# modul_analogin.net
KiCad netlist of a schematic drawn in EAGLE
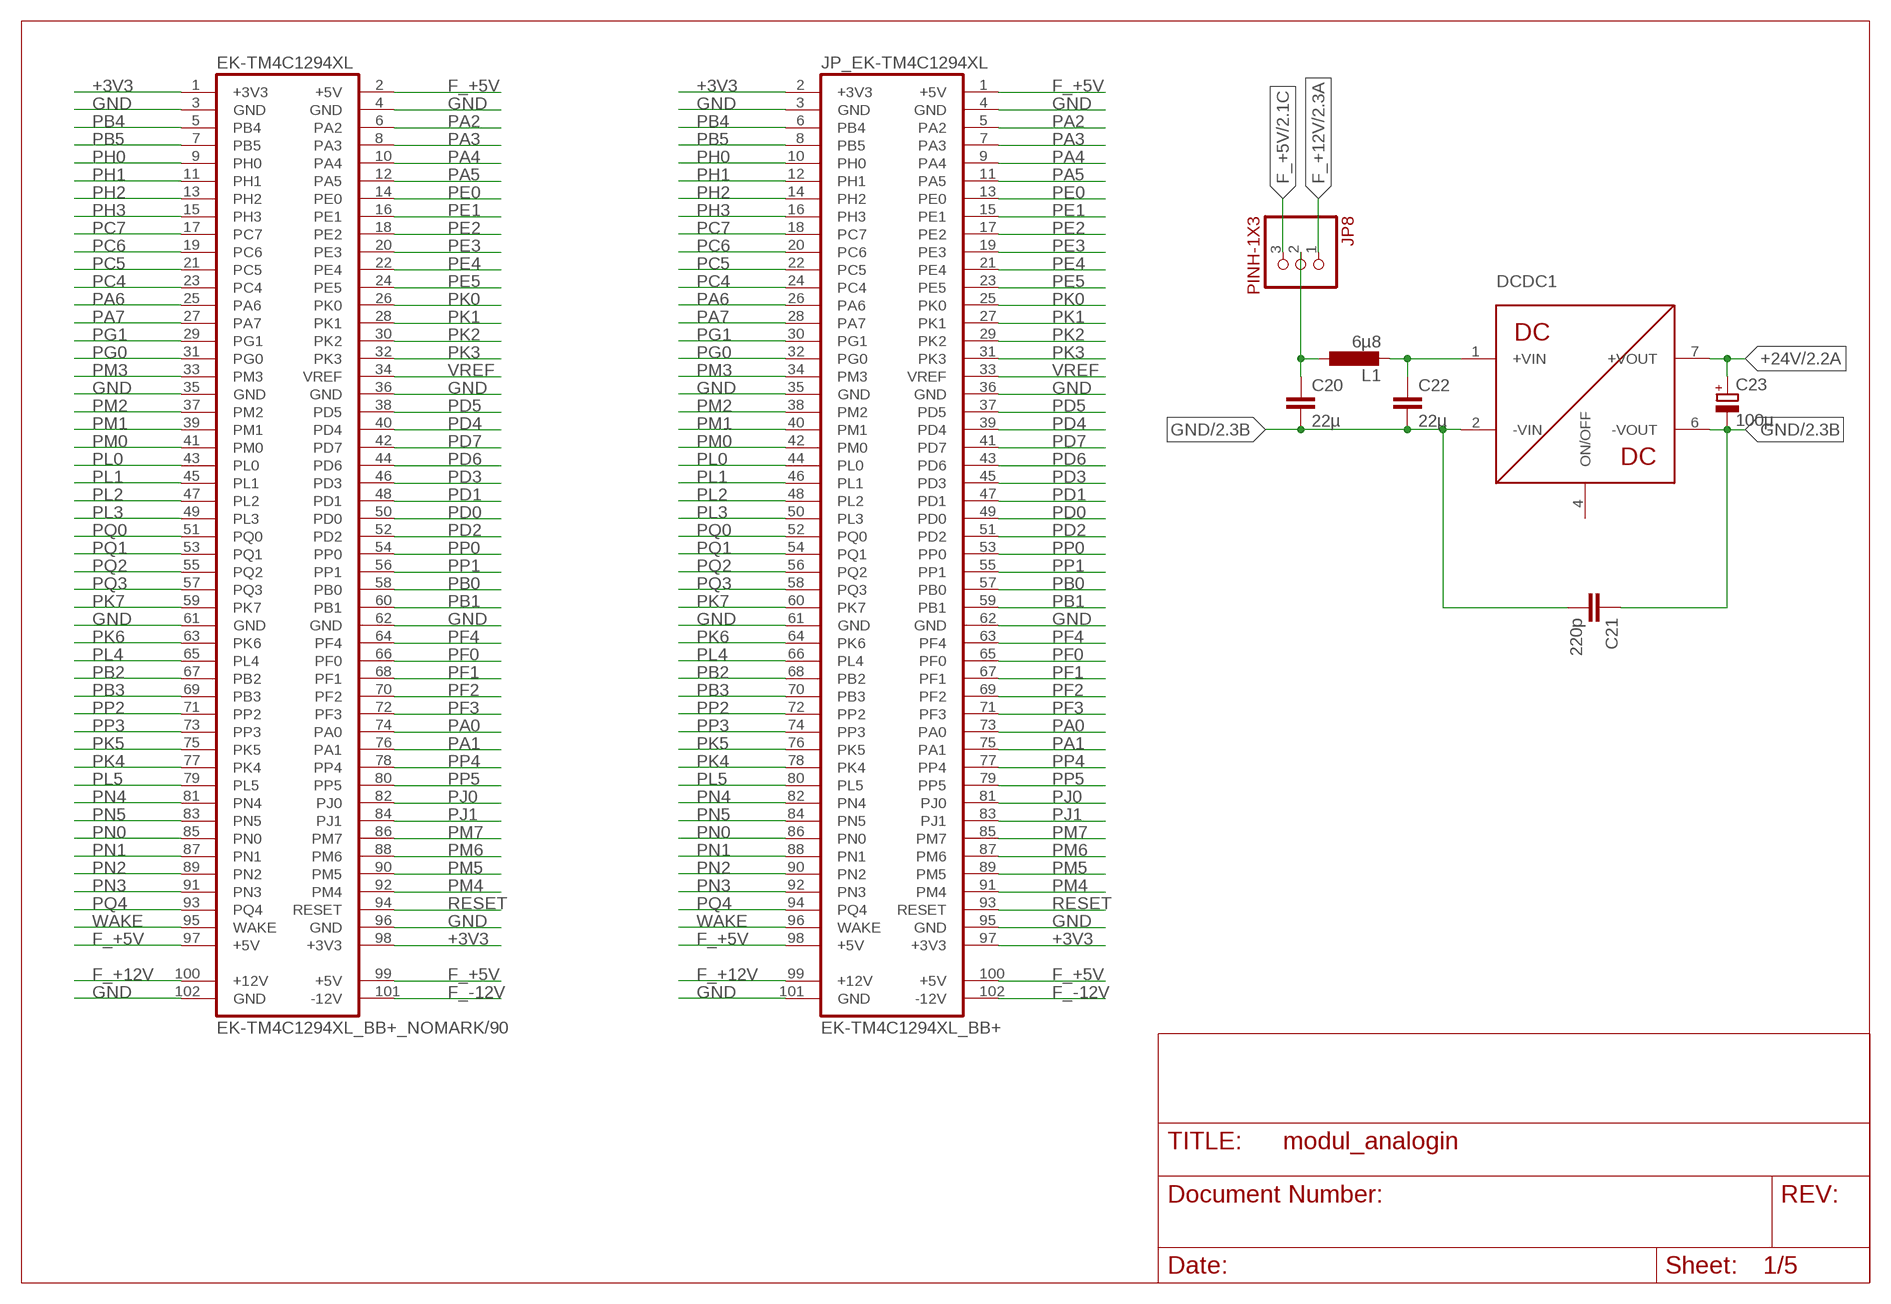
[diagram p0: schematic, sheet 1]
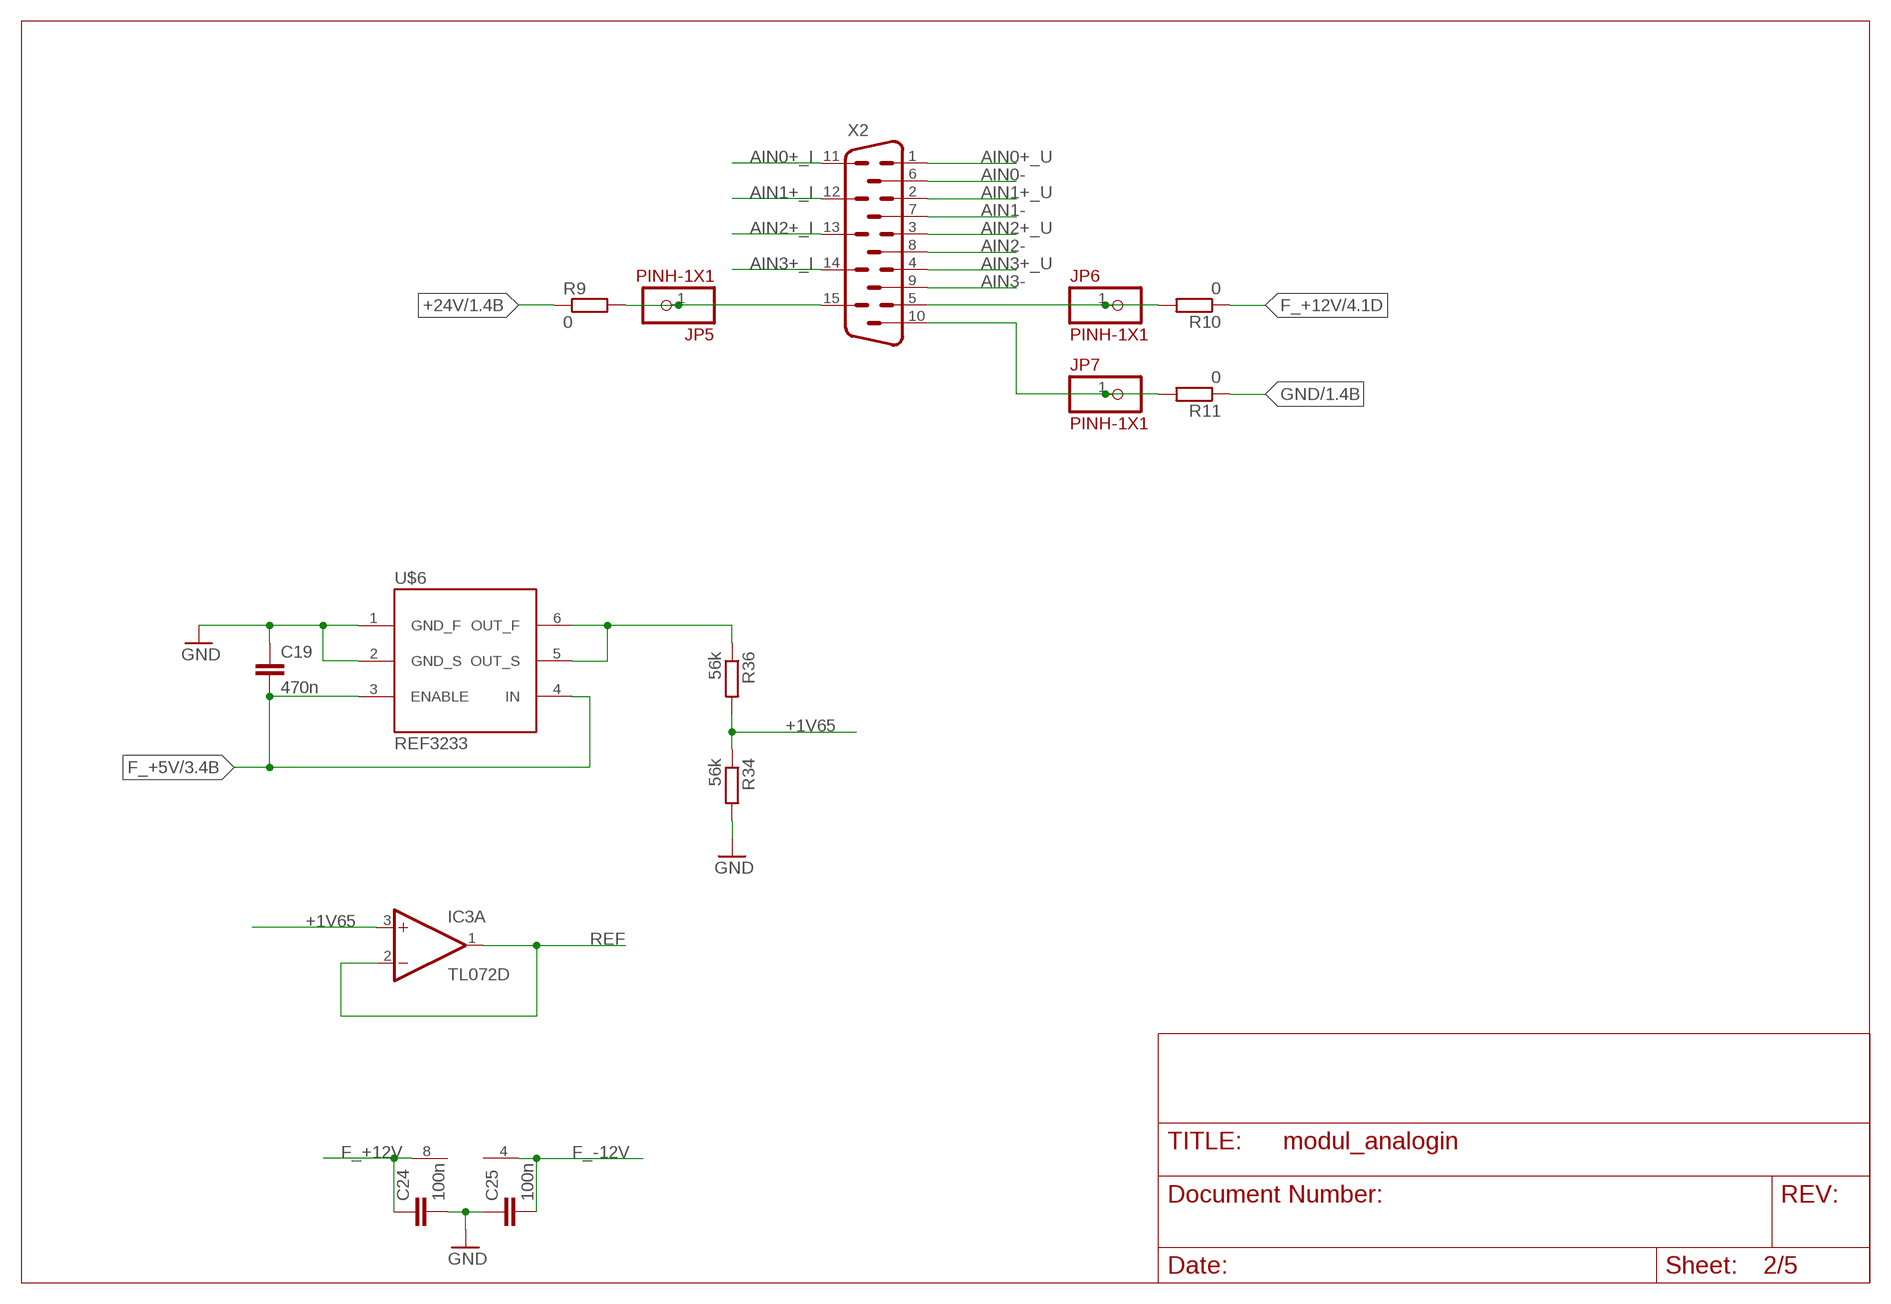
[diagram p1: schematic, sheet 2]
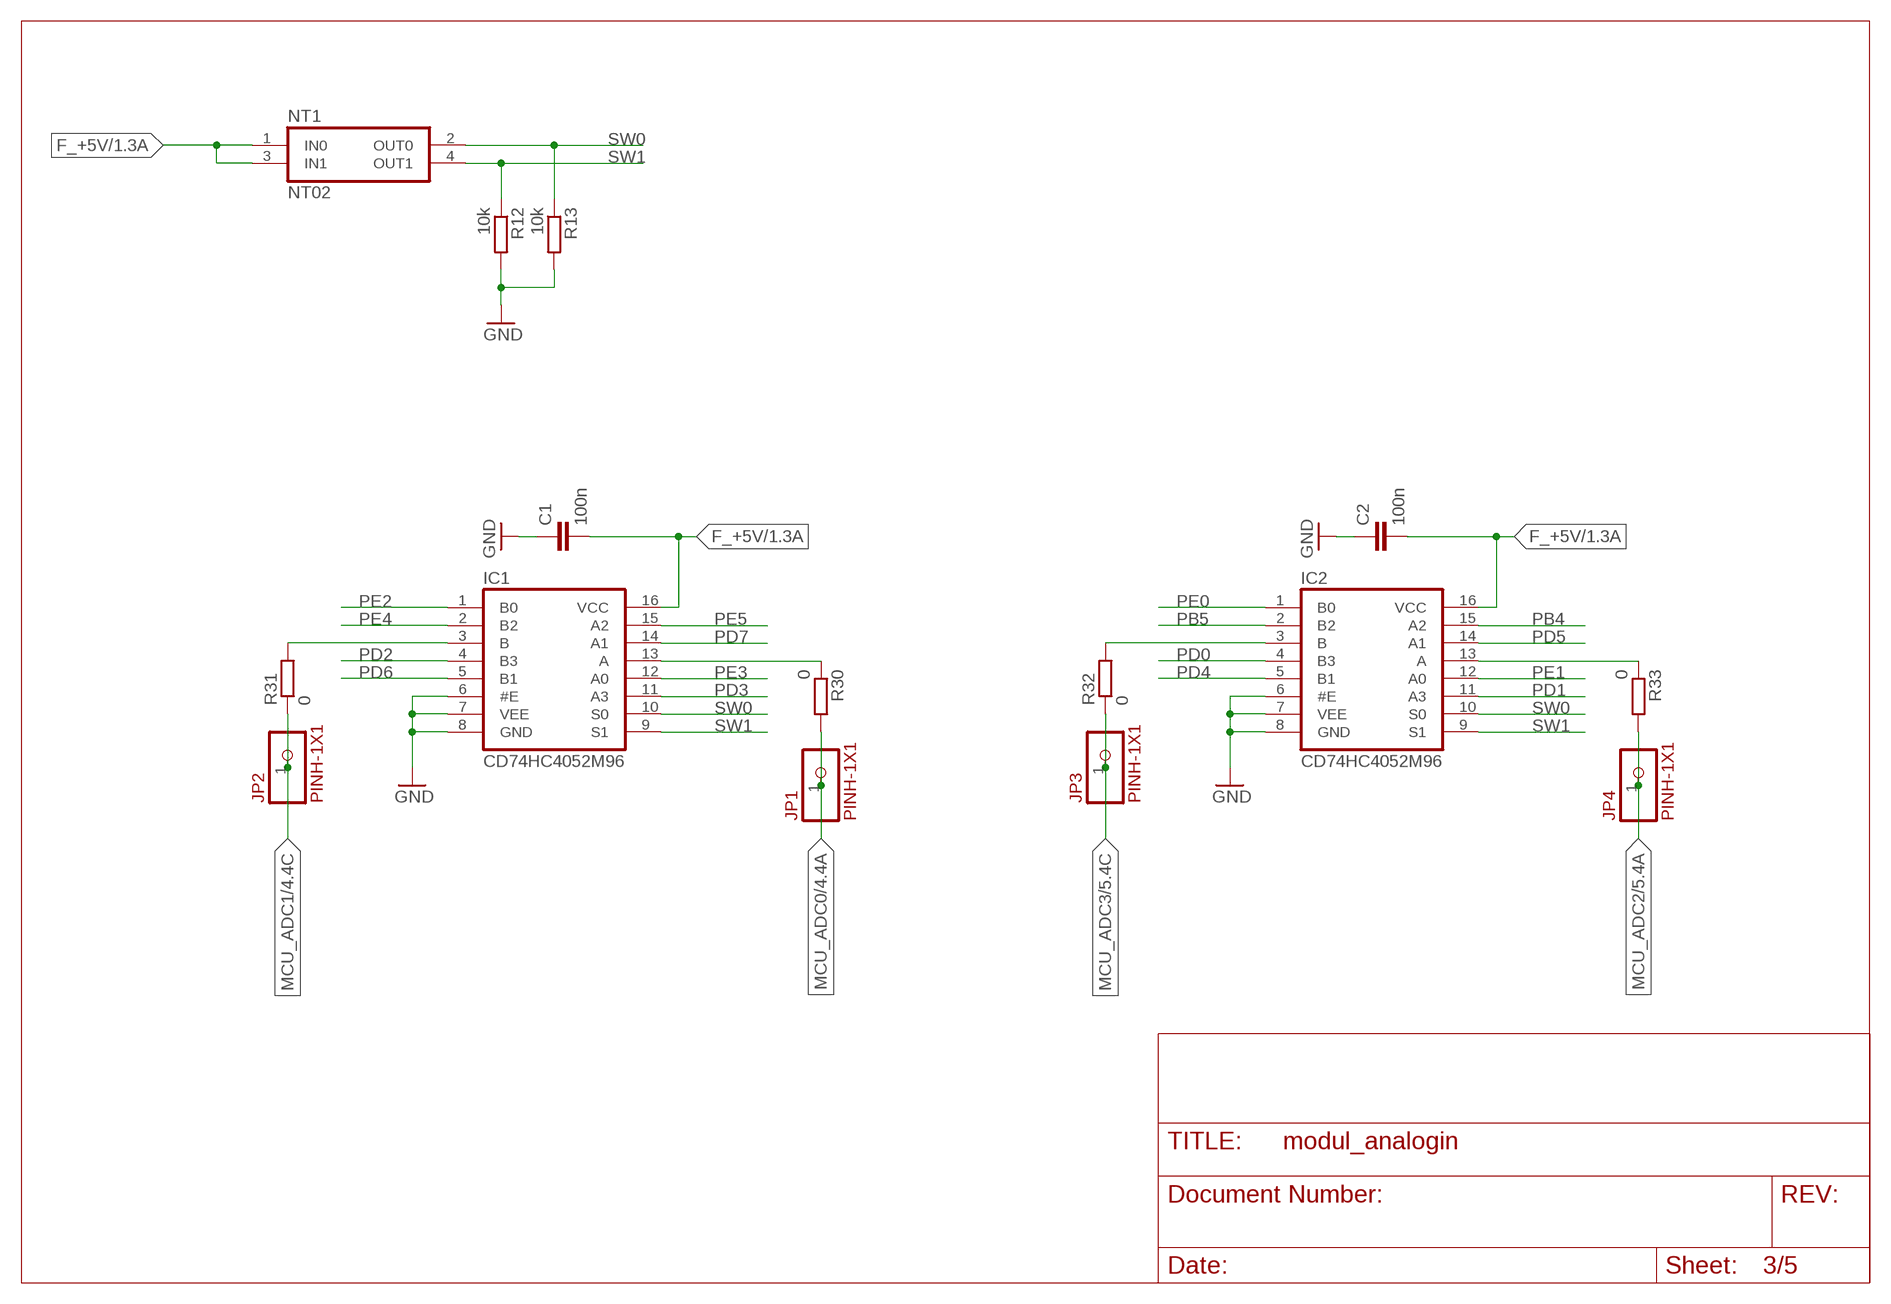
[diagram p2: schematic, sheet 3]
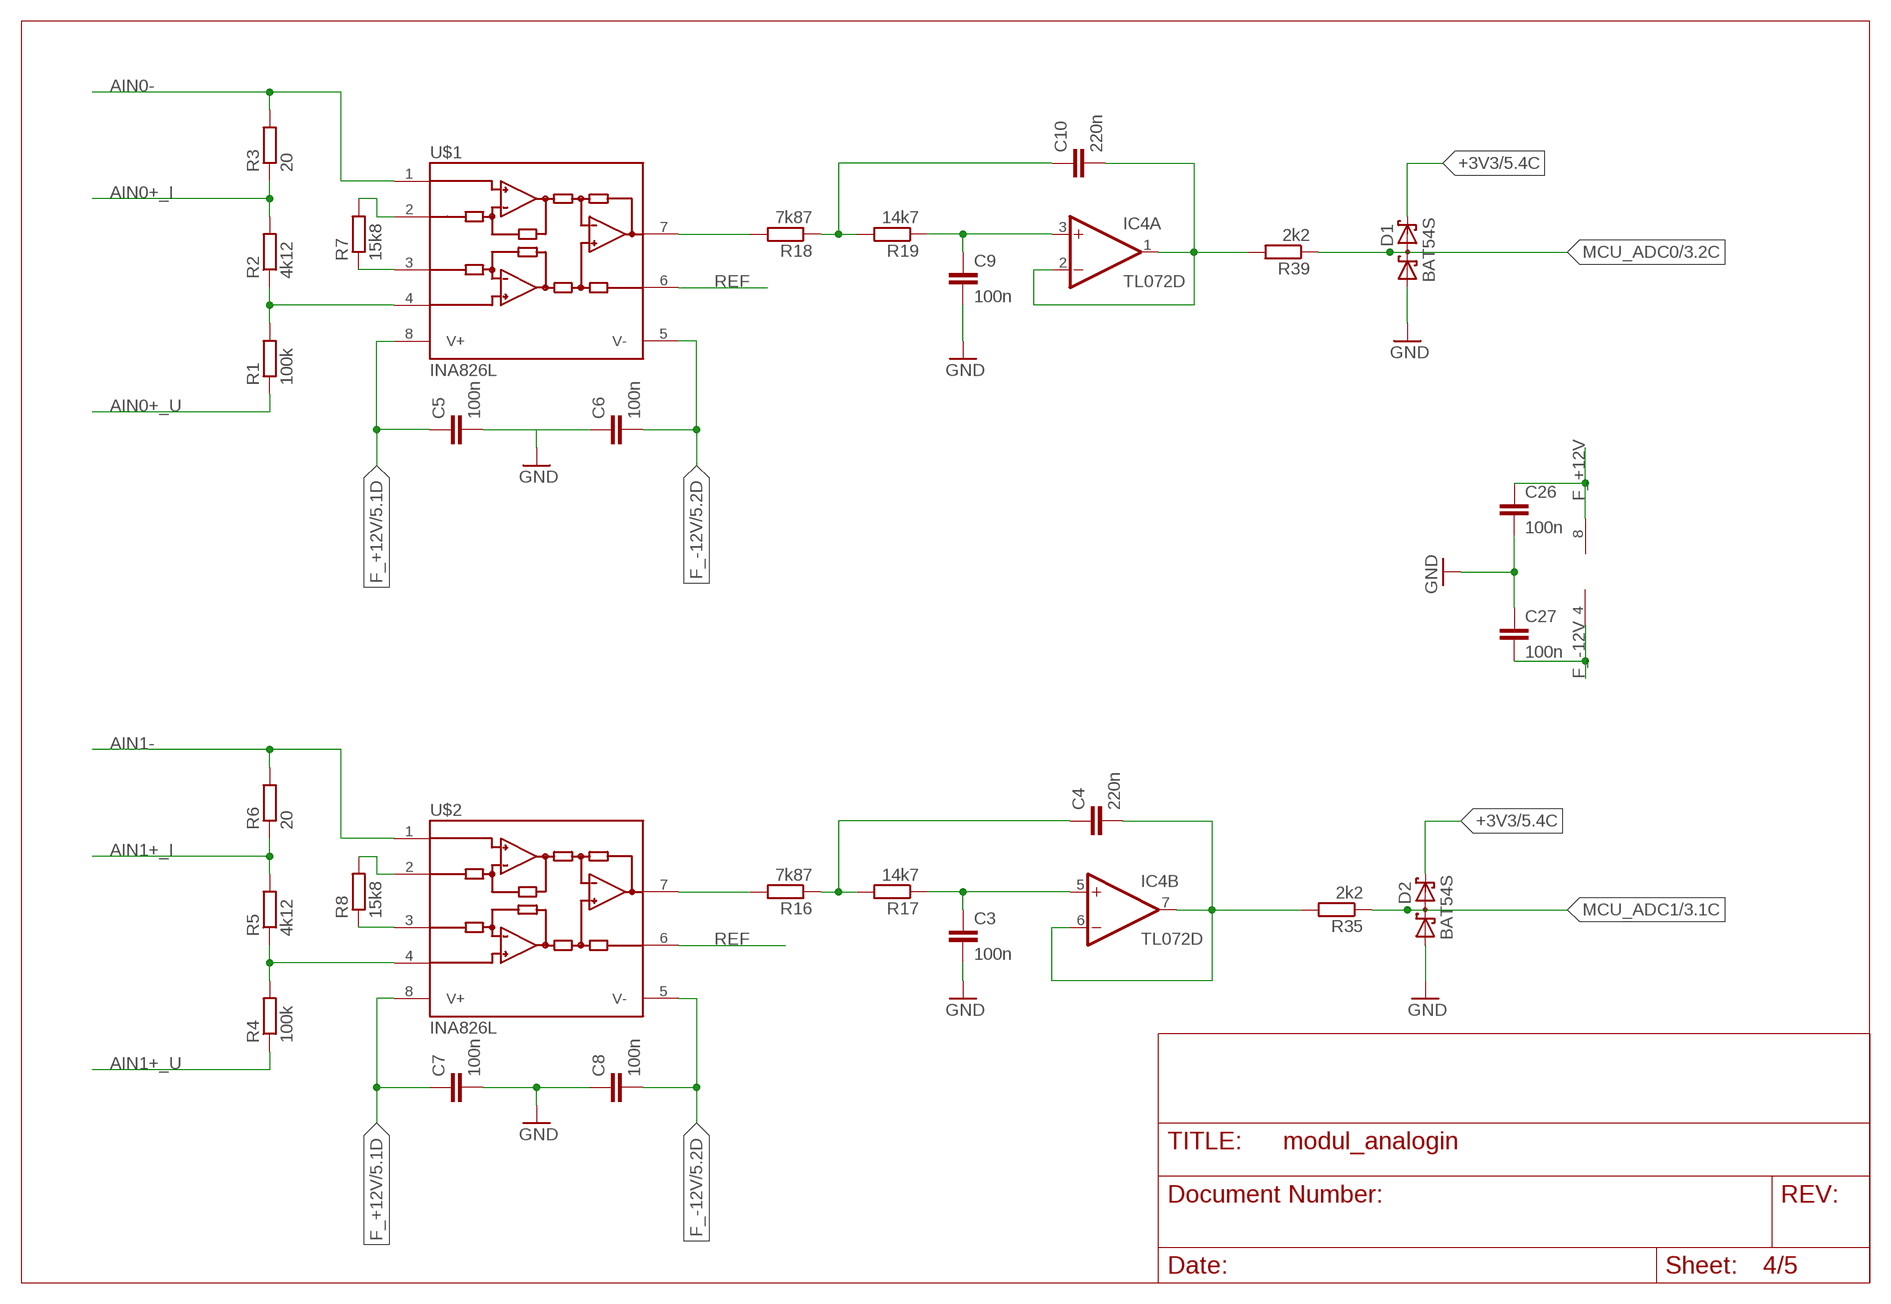
[diagram p3: schematic, sheet 4]
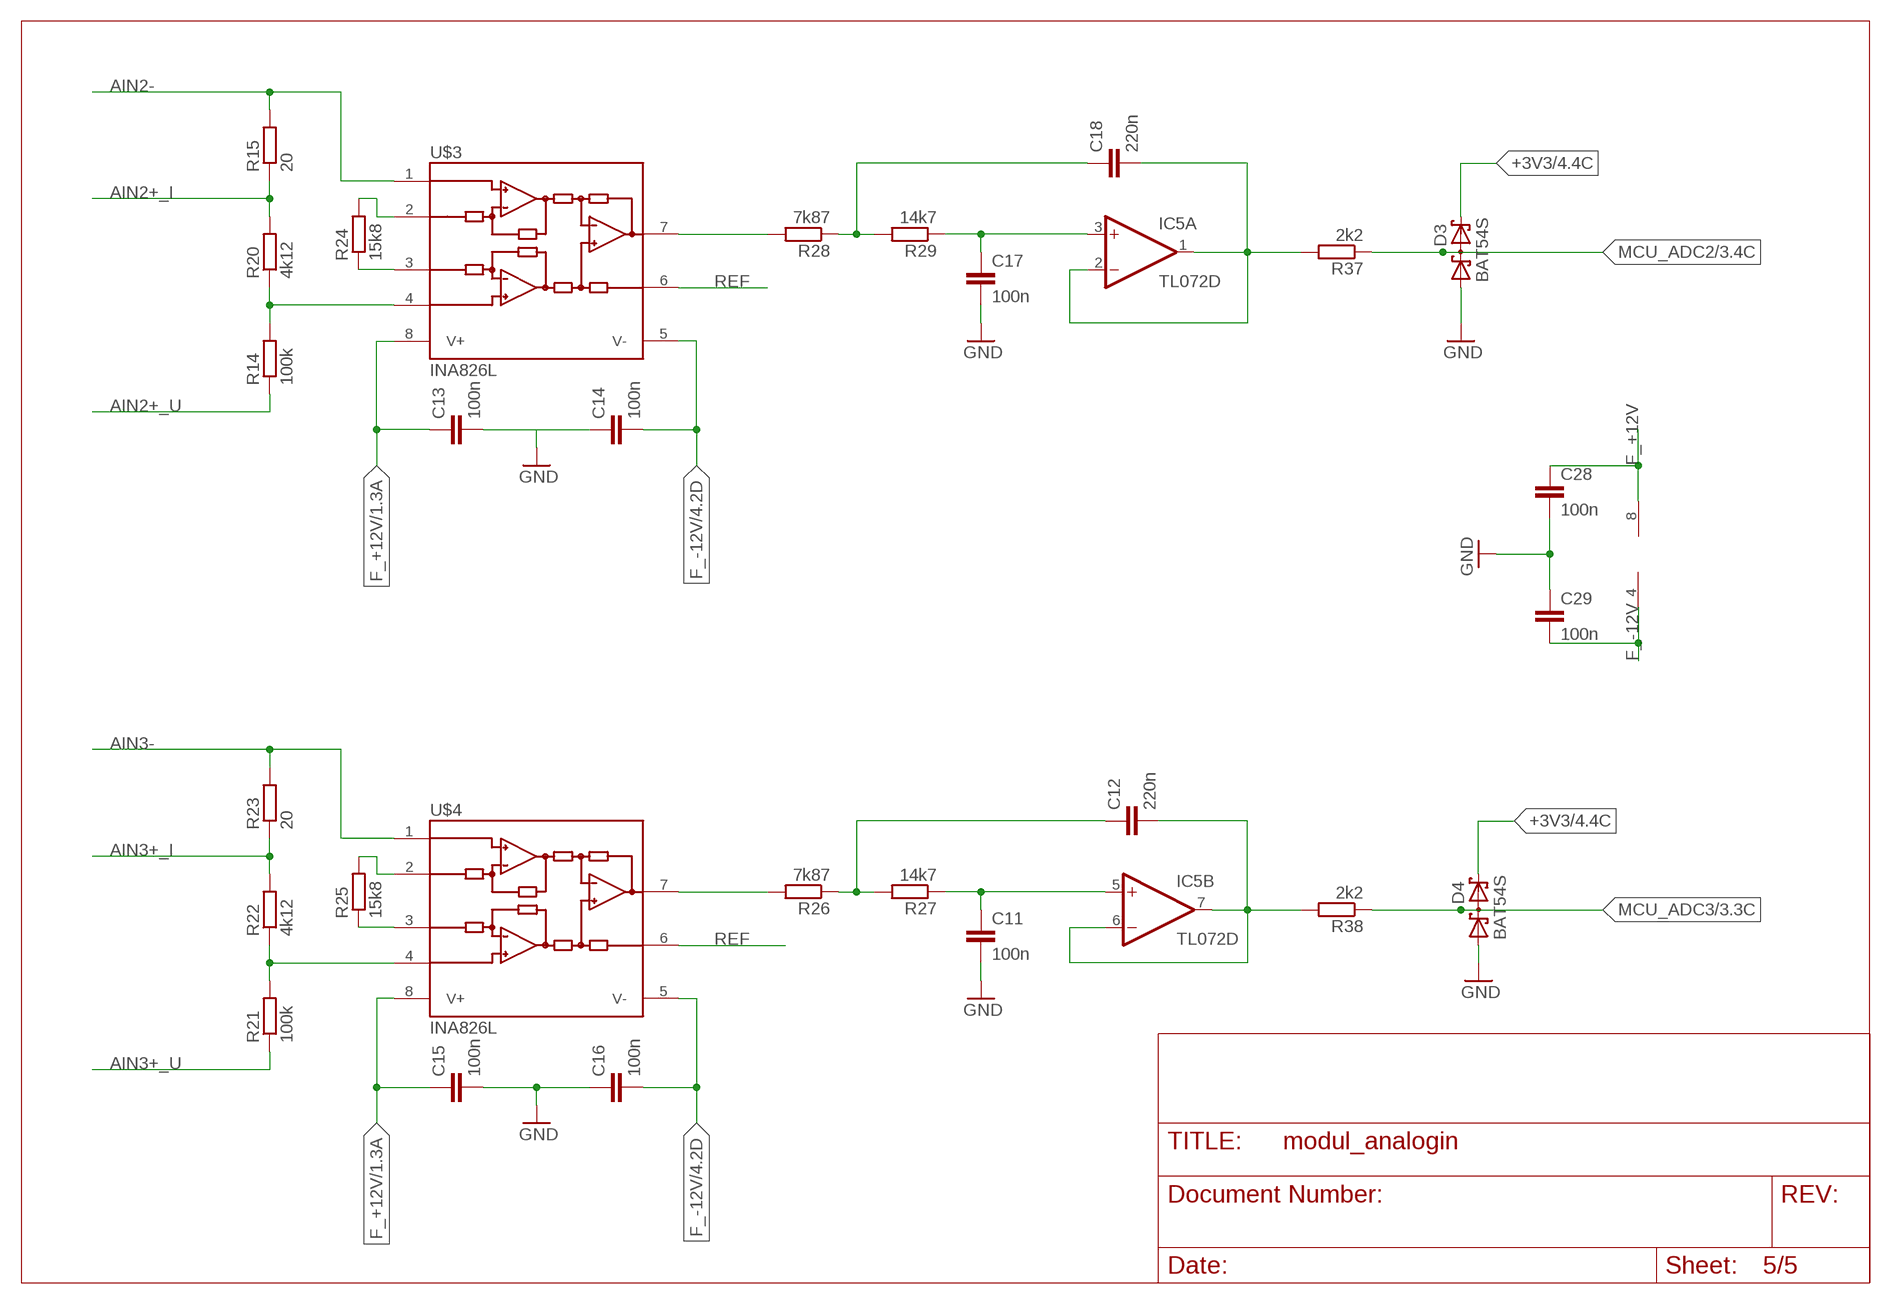
[diagram p4: schematic, sheet 5]

(export (version "E")
  (design (tool "Eeschema 10.0.6"))
  (components
    (comp (ref "C11")
      (value "100n")
      (footprint "eagle-import:C0805")
      (libsource (lib "eagle-import") (part "resistor_C-EUC0805"))
    )
    (comp (ref "C12")
      (value "220n")
      (footprint "eagle-import:C0805")
      (libsource (lib "eagle-import") (part "resistor_C-EUC0805"))
    )
    (comp (ref "C13")
      (value "100n")
      (footprint "eagle-import:C0805")
      (libsource (lib "eagle-import") (part "resistor_C-EUC0805"))
    )
    (comp (ref "C14")
      (value "100n")
      (footprint "eagle-import:C0805")
      (libsource (lib "eagle-import") (part "resistor_C-EUC0805"))
    )
    (comp (ref "C15")
      (value "100n")
      (footprint "eagle-import:C0805")
      (libsource (lib "eagle-import") (part "resistor_C-EUC0805"))
    )
    (comp (ref "C16")
      (value "100n")
      (footprint "eagle-import:C0805")
      (libsource (lib "eagle-import") (part "resistor_C-EUC0805"))
    )
    (comp (ref "C17")
      (value "100n")
      (footprint "eagle-import:C0805")
      (libsource (lib "eagle-import") (part "resistor_C-EUC0805"))
    )
    (comp (ref "C18")
      (value "220n")
      (footprint "eagle-import:C0805")
      (libsource (lib "eagle-import") (part "resistor_C-EUC0805"))
    )
    (comp (ref "C28")
      (value "100n")
      (footprint "eagle-import:C0805")
      (libsource (lib "eagle-import") (part "resistor_C-EUC0805"))
    )
    (comp (ref "C29")
      (value "100n")
      (footprint "eagle-import:C0805")
      (libsource (lib "eagle-import") (part "resistor_C-EUC0805"))
    )
    (comp (ref "D3")
      (value "BAT54S")
      (footprint "eagle-import:SOT23")
      (libsource (lib "eagle-import") (part "BAT54S"))
    )
    (comp (ref "D4")
      (value "BAT54S")
      (footprint "eagle-import:SOT23")
      (libsource (lib "eagle-import") (part "BAT54S"))
    )
    (comp (ref "IC5")
      (value "TL072D")
      (footprint "eagle-import:SO08")
      (libsource (lib "eagle-import") (part "TL072D"))
    )
    (comp (ref "R14")
      (value "100k")
      (footprint "eagle-import:R0805")
      (libsource (lib "eagle-import") (part "R-EU_R0805"))
    )
    (comp (ref "R15")
      (value "20")
      (footprint "eagle-import:R0805")
      (libsource (lib "eagle-import") (part "R-EU_R0805"))
    )
    (comp (ref "R20")
      (value "4k12")
      (footprint "eagle-import:R0805")
      (libsource (lib "eagle-import") (part "R-EU_R0805"))
    )
    (comp (ref "R21")
      (value "100k")
      (footprint "eagle-import:R0805")
      (libsource (lib "eagle-import") (part "R-EU_R0805"))
    )
    (comp (ref "R22")
      (value "4k12")
      (footprint "eagle-import:R0805")
      (libsource (lib "eagle-import") (part "R-EU_R0805"))
    )
    (comp (ref "R23")
      (value "20")
      (footprint "eagle-import:R0805")
      (libsource (lib "eagle-import") (part "R-EU_R0805"))
    )
    (comp (ref "R24")
      (value "15k8")
      (footprint "eagle-import:R0805")
      (libsource (lib "eagle-import") (part "R-EU_R0805"))
    )
    (comp (ref "R25")
      (value "15k8")
      (footprint "eagle-import:R0805")
      (libsource (lib "eagle-import") (part "R-EU_R0805"))
    )
    (comp (ref "R26")
      (value "7k87")
      (footprint "eagle-import:R0805")
      (libsource (lib "eagle-import") (part "R-EU_R0805"))
    )
    (comp (ref "R27")
      (value "14k7")
      (footprint "eagle-import:R0805")
      (libsource (lib "eagle-import") (part "R-EU_R0805"))
    )
    (comp (ref "R28")
      (value "7k87")
      (footprint "eagle-import:R0805")
      (libsource (lib "eagle-import") (part "R-EU_R0805"))
    )
    (comp (ref "R29")
      (value "14k7")
      (footprint "eagle-import:R0805")
      (libsource (lib "eagle-import") (part "R-EU_R0805"))
    )
    (comp (ref "R37")
      (value "2k2")
      (footprint "eagle-import:R0805")
      (libsource (lib "eagle-import") (part "R-EU_R0805"))
    )
    (comp (ref "R38")
      (value "2k2")
      (footprint "eagle-import:R0805")
      (libsource (lib "eagle-import") (part "R-EU_R0805"))
    )
    (comp (ref "U$3")
      (value "INA826L")
      (footprint "eagle-import:DGK_S-PDSO-G8")
      (libsource (lib "eagle-import") (part "INA826L"))
    )
    (comp (ref "U$4")
      (value "INA826L")
      (footprint "eagle-import:DGK_S-PDSO-G8")
      (libsource (lib "eagle-import") (part "INA826L"))
    )
    (comp (ref "C20")
      (value "22µ")
      (footprint "eagle-import:C1206")
      (libsource (lib "eagle-import") (part "C-EUC1206"))
    )
    (comp (ref "C21")
      (value "220p")
      (footprint "eagle-import:C1808")
      (libsource (lib "eagle-import") (part "C-EUC1808"))
    )
    (comp (ref "C22")
      (value "22µ")
      (footprint "eagle-import:C1206")
      (libsource (lib "eagle-import") (part "C-EUC1206"))
    )
    (comp (ref "C23")
      (value "100µ")
      (footprint "eagle-import:E2,5-6")
      (libsource (lib "eagle-import") (part "CPOL-EUE2.5-6"))
    )
    (comp (ref "DCDC1")
      (value "TDN3WI")
      (footprint "eagle-import:TDN_XWI")
      (libsource (lib "eagle-import") (part "TDN3WI"))
    )
    (comp (ref "EK-TM4C1294XL")
      (value "EK-TM4C1294XL_BB+_NOMARK/90")
      (footprint "eagle-import:EK-TM4C1294XL_BB+_NOMARK_90")
      (libsource (lib "eagle-import") (part "EK-TM4C1294XL_BB+_NOMARK/90"))
    )
    (comp (ref "JP8")
      (value "PINH-1X3")
      (footprint "eagle-import:1X3")
      (libsource (lib "eagle-import") (part "PINH-1X3"))
    )
    (comp (ref "JP_EK-TM4C1294XL")
      (value "EK-TM4C1294XL_BB+")
      (footprint "eagle-import:EK-TM4C1294XL_BB+")
      (libsource (lib "eagle-import") (part "EK-TM4C1294XL_BB+"))
    )
    (comp (ref "L1")
      (value "6µ8")
      (footprint "eagle-import:L1812")
      (libsource (lib "eagle-import") (part "L-EUL1812"))
    )
    (comp (ref "C3")
      (value "100n")
      (footprint "eagle-import:C0805")
      (libsource (lib "eagle-import") (part "resistor_C-EUC0805"))
    )
    (comp (ref "C4")
      (value "220n")
      (footprint "eagle-import:C0805")
      (libsource (lib "eagle-import") (part "resistor_C-EUC0805"))
    )
    (comp (ref "C5")
      (value "100n")
      (footprint "eagle-import:C0805")
      (libsource (lib "eagle-import") (part "resistor_C-EUC0805"))
    )
    (comp (ref "C6")
      (value "100n")
      (footprint "eagle-import:C0805")
      (libsource (lib "eagle-import") (part "resistor_C-EUC0805"))
    )
    (comp (ref "C7")
      (value "100n")
      (footprint "eagle-import:C0805")
      (libsource (lib "eagle-import") (part "resistor_C-EUC0805"))
    )
    (comp (ref "C8")
      (value "100n")
      (footprint "eagle-import:C0805")
      (libsource (lib "eagle-import") (part "resistor_C-EUC0805"))
    )
    (comp (ref "C9")
      (value "100n")
      (footprint "eagle-import:C0805")
      (libsource (lib "eagle-import") (part "resistor_C-EUC0805"))
    )
    (comp (ref "C10")
      (value "220n")
      (footprint "eagle-import:C0805")
      (libsource (lib "eagle-import") (part "resistor_C-EUC0805"))
    )
    (comp (ref "C26")
      (value "100n")
      (footprint "eagle-import:C0805")
      (libsource (lib "eagle-import") (part "resistor_C-EUC0805"))
    )
    (comp (ref "C27")
      (value "100n")
      (footprint "eagle-import:C0805")
      (libsource (lib "eagle-import") (part "resistor_C-EUC0805"))
    )
    (comp (ref "D1")
      (value "BAT54S")
      (footprint "eagle-import:SOT23")
      (libsource (lib "eagle-import") (part "BAT54S"))
    )
    (comp (ref "D2")
      (value "BAT54S")
      (footprint "eagle-import:SOT23")
      (libsource (lib "eagle-import") (part "BAT54S"))
    )
    (comp (ref "IC4")
      (value "TL072D")
      (footprint "eagle-import:SO08")
      (libsource (lib "eagle-import") (part "TL072D"))
    )
    (comp (ref "R1")
      (value "100k")
      (footprint "eagle-import:R0805")
      (libsource (lib "eagle-import") (part "R-EU_R0805"))
    )
    (comp (ref "R2")
      (value "4k12")
      (footprint "eagle-import:R0805")
      (libsource (lib "eagle-import") (part "R-EU_R0805"))
    )
    (comp (ref "R3")
      (value "20")
      (footprint "eagle-import:R0805")
      (libsource (lib "eagle-import") (part "R-EU_R0805"))
    )
    (comp (ref "R4")
      (value "100k")
      (footprint "eagle-import:R0805")
      (libsource (lib "eagle-import") (part "R-EU_R0805"))
    )
    (comp (ref "R5")
      (value "4k12")
      (footprint "eagle-import:R0805")
      (libsource (lib "eagle-import") (part "R-EU_R0805"))
    )
    (comp (ref "R6")
      (value "20")
      (footprint "eagle-import:R0805")
      (libsource (lib "eagle-import") (part "R-EU_R0805"))
    )
    (comp (ref "R7")
      (value "15k8")
      (footprint "eagle-import:R0805")
      (libsource (lib "eagle-import") (part "R-EU_R0805"))
    )
    (comp (ref "R8")
      (value "15k8")
      (footprint "eagle-import:R0805")
      (libsource (lib "eagle-import") (part "R-EU_R0805"))
    )
    (comp (ref "R16")
      (value "7k87")
      (footprint "eagle-import:R0805")
      (libsource (lib "eagle-import") (part "R-EU_R0805"))
    )
    (comp (ref "R17")
      (value "14k7")
      (footprint "eagle-import:R0805")
      (libsource (lib "eagle-import") (part "R-EU_R0805"))
    )
    (comp (ref "R18")
      (value "7k87")
      (footprint "eagle-import:R0805")
      (libsource (lib "eagle-import") (part "R-EU_R0805"))
    )
    (comp (ref "R19")
      (value "14k7")
      (footprint "eagle-import:R0805")
      (libsource (lib "eagle-import") (part "R-EU_R0805"))
    )
    (comp (ref "R35")
      (value "2k2")
      (footprint "eagle-import:R0805")
      (libsource (lib "eagle-import") (part "R-EU_R0805"))
    )
    (comp (ref "R39")
      (value "2k2")
      (footprint "eagle-import:R0805")
      (libsource (lib "eagle-import") (part "R-EU_R0805"))
    )
    (comp (ref "U$1")
      (value "INA826L")
      (footprint "eagle-import:DGK_S-PDSO-G8")
      (libsource (lib "eagle-import") (part "INA826L"))
    )
    (comp (ref "U$2")
      (value "INA826L")
      (footprint "eagle-import:DGK_S-PDSO-G8")
      (libsource (lib "eagle-import") (part "INA826L"))
    )
    (comp (ref "C19")
      (value "470n")
      (footprint "eagle-import:C0805")
      (libsource (lib "eagle-import") (part "resistor_C-EUC0805"))
    )
    (comp (ref "C24")
      (value "100n")
      (footprint "eagle-import:C0805")
      (libsource (lib "eagle-import") (part "resistor_C-EUC0805"))
    )
    (comp (ref "C25")
      (value "100n")
      (footprint "eagle-import:C0805")
      (libsource (lib "eagle-import") (part "resistor_C-EUC0805"))
    )
    (comp (ref "IC3")
      (value "TL072D")
      (footprint "eagle-import:SO08")
      (libsource (lib "eagle-import") (part "TL072D"))
    )
    (comp (ref "JP5")
      (value "PINH-1X1")
      (footprint "eagle-import:1X1")
      (libsource (lib "eagle-import") (part "PINH-1X1"))
    )
    (comp (ref "JP6")
      (value "PINH-1X1")
      (footprint "eagle-import:1X1")
      (libsource (lib "eagle-import") (part "PINH-1X1"))
    )
    (comp (ref "JP7")
      (value "PINH-1X1")
      (footprint "eagle-import:1X1")
      (libsource (lib "eagle-import") (part "PINH-1X1"))
    )
    (comp (ref "R9")
      (value "0")
      (footprint "eagle-import:R0805")
      (libsource (lib "eagle-import") (part "R-EU_R0805"))
    )
    (comp (ref "R10")
      (value "0")
      (footprint "eagle-import:R0805")
      (libsource (lib "eagle-import") (part "R-EU_R0805"))
    )
    (comp (ref "R11")
      (value "0")
      (footprint "eagle-import:R0805")
      (libsource (lib "eagle-import") (part "R-EU_R0805"))
    )
    (comp (ref "R34")
      (value "56k")
      (footprint "eagle-import:R0805")
      (libsource (lib "eagle-import") (part "R-EU_R0805"))
    )
    (comp (ref "R36")
      (value "56k")
      (footprint "eagle-import:R0805")
      (libsource (lib "eagle-import") (part "R-EU_R0805"))
    )
    (comp (ref "U$6")
      (value "REF3233")
      (footprint "eagle-import:SOT-23-6_DBV")
      (libsource (lib "eagle-import") (part "REF3233"))
    )
    (comp (ref "X2")
      (value "HM15H")
      (footprint "eagle-import:HDM15H")
      (libsource (lib "eagle-import") (part "HM15H"))
    )
    (comp (ref "C1")
      (value "100n")
      (footprint "eagle-import:C0805")
      (libsource (lib "eagle-import") (part "resistor_C-EUC0805"))
    )
    (comp (ref "C2")
      (value "100n")
      (footprint "eagle-import:C0805")
      (libsource (lib "eagle-import") (part "resistor_C-EUC0805"))
    )
    (comp (ref "IC1")
      (value "CD74HC4052M96")
      (footprint "eagle-import:SOIC16_D")
      (libsource (lib "eagle-import") (part "CD74HC4052M96"))
    )
    (comp (ref "IC2")
      (value "CD74HC4052M96")
      (footprint "eagle-import:SOIC16_D")
      (libsource (lib "eagle-import") (part "CD74HC4052M96"))
    )
    (comp (ref "JP1")
      (value "PINH-1X1")
      (footprint "eagle-import:1X1")
      (libsource (lib "eagle-import") (part "PINH-1X1"))
    )
    (comp (ref "JP2")
      (value "PINH-1X1")
      (footprint "eagle-import:1X1")
      (libsource (lib "eagle-import") (part "PINH-1X1"))
    )
    (comp (ref "JP3")
      (value "PINH-1X1")
      (footprint "eagle-import:1X1")
      (libsource (lib "eagle-import") (part "PINH-1X1"))
    )
    (comp (ref "JP4")
      (value "PINH-1X1")
      (footprint "eagle-import:1X1")
      (libsource (lib "eagle-import") (part "PINH-1X1"))
    )
    (comp (ref "NT1")
      (value "NT02")
      (footprint "eagle-import:NT02")
      (libsource (lib "eagle-import") (part "NT02"))
    )
    (comp (ref "R12")
      (value "10k")
      (footprint "eagle-import:R0805")
      (libsource (lib "eagle-import") (part "R-EU_R0805"))
    )
    (comp (ref "R13")
      (value "10k")
      (footprint "eagle-import:R0805")
      (libsource (lib "eagle-import") (part "R-EU_R0805"))
    )
    (comp (ref "R30")
      (value "0")
      (footprint "eagle-import:R0805")
      (libsource (lib "eagle-import") (part "R-EU_R0805"))
    )
    (comp (ref "R31")
      (value "0")
      (footprint "eagle-import:R0805")
      (libsource (lib "eagle-import") (part "R-EU_R0805"))
    )
    (comp (ref "R32")
      (value "0")
      (footprint "eagle-import:R0805")
      (libsource (lib "eagle-import") (part "R-EU_R0805"))
    )
    (comp (ref "R33")
      (value "0")
      (footprint "eagle-import:R0805")
      (libsource (lib "eagle-import") (part "R-EU_R0805"))
    )
  )
  (nets
    (net (code "1") (name "+1V65") (class "Default")
      (node (ref "IC3") (pin "3") (pinfunction "+IN_3") (pintype "input"))
      (node (ref "R34") (pin "1") (pinfunction "1_1") (pintype "passive"))
      (node (ref "R36") (pin "2") (pinfunction "2_2") (pintype "passive"))
    )
    (net (code "2") (name "+3V3") (class "Default")
      (node (ref "D1") (pin "2") (pinfunction "C2_2") (pintype "passive"))
      (node (ref "D2") (pin "2") (pinfunction "C2_2") (pintype "passive"))
      (node (ref "D3") (pin "2") (pinfunction "C2_2") (pintype "passive"))
      (node (ref "D4") (pin "2") (pinfunction "C2_2") (pintype "passive"))
      (node (ref "EK-TM4C1294XL") (pin "1") (pinfunction "+3V3_1") (pintype "power_in"))
      (node (ref "EK-TM4C1294XL") (pin "98") (pinfunction "+3V3_98") (pintype "power_in"))
      (node (ref "JP_EK-TM4C1294XL") (pin "2") (pinfunction "+3V3_2") (pintype "power_in"))
      (node (ref "JP_EK-TM4C1294XL") (pin "97") (pinfunction "+3V3_97") (pintype "power_in"))
    )
    (net (code "3") (name "+24V") (class "Default")
      (node (ref "C23") (pin "+") (pinfunction "+_+") (pintype "passive"))
      (node (ref "DCDC1") (pin "7") (pinfunction "+VOUT_7") (pintype "power_in"))
      (node (ref "R9") (pin "1") (pinfunction "1_1") (pintype "passive"))
    )
    (net (code "4") (name "AIN0+_I") (class "Default")
      (node (ref "R2") (pin "2") (pinfunction "2_2") (pintype "passive"))
      (node (ref "R3") (pin "1") (pinfunction "1_1") (pintype "passive"))
      (node (ref "X2") (pin "11") (pinfunction "11_11") (pintype "passive"))
    )
    (net (code "5") (name "AIN0+_U") (class "Default")
      (node (ref "R1") (pin "1") (pinfunction "1_1") (pintype "passive"))
      (node (ref "X2") (pin "1") (pinfunction "1_1") (pintype "passive"))
    )
    (net (code "6") (name "AIN0-") (class "Default")
      (node (ref "R3") (pin "2") (pinfunction "2_2") (pintype "passive"))
      (node (ref "U$1") (pin "1") (pinfunction "-IN_1") (pintype "input"))
      (node (ref "X2") (pin "6") (pinfunction "6_6") (pintype "passive"))
    )
    (net (code "7") (name "AIN1+_I") (class "Default")
      (node (ref "R5") (pin "2") (pinfunction "2_2") (pintype "passive"))
      (node (ref "R6") (pin "1") (pinfunction "1_1") (pintype "passive"))
      (node (ref "X2") (pin "12") (pinfunction "12_12") (pintype "passive"))
    )
    (net (code "8") (name "AIN1+_U") (class "Default")
      (node (ref "R4") (pin "1") (pinfunction "1_1") (pintype "passive"))
      (node (ref "X2") (pin "2") (pinfunction "2_2") (pintype "passive"))
    )
    (net (code "9") (name "AIN1-") (class "Default")
      (node (ref "R6") (pin "2") (pinfunction "2_2") (pintype "passive"))
      (node (ref "U$2") (pin "1") (pinfunction "-IN_1") (pintype "input"))
      (node (ref "X2") (pin "7") (pinfunction "7_7") (pintype "passive"))
    )
    (net (code "10") (name "AIN2+_I") (class "Default")
      (node (ref "R15") (pin "1") (pinfunction "1_1") (pintype "passive"))
      (node (ref "R20") (pin "2") (pinfunction "2_2") (pintype "passive"))
      (node (ref "X2") (pin "13") (pinfunction "13_13") (pintype "passive"))
    )
    (net (code "11") (name "AIN2+_U") (class "Default")
      (node (ref "R14") (pin "1") (pinfunction "1_1") (pintype "passive"))
      (node (ref "X2") (pin "3") (pinfunction "3_3") (pintype "passive"))
    )
    (net (code "12") (name "AIN2-") (class "Default")
      (node (ref "R15") (pin "2") (pinfunction "2_2") (pintype "passive"))
      (node (ref "U$3") (pin "1") (pinfunction "-IN_1") (pintype "input"))
      (node (ref "X2") (pin "8") (pinfunction "8_8") (pintype "passive"))
    )
    (net (code "13") (name "AIN3+_I") (class "Default")
      (node (ref "R22") (pin "2") (pinfunction "2_2") (pintype "passive"))
      (node (ref "R23") (pin "1") (pinfunction "1_1") (pintype "passive"))
      (node (ref "X2") (pin "14") (pinfunction "14_14") (pintype "passive"))
    )
    (net (code "14") (name "AIN3+_U") (class "Default")
      (node (ref "R21") (pin "1") (pinfunction "1_1") (pintype "passive"))
      (node (ref "X2") (pin "4") (pinfunction "4_4") (pintype "passive"))
    )
    (net (code "15") (name "AIN3-") (class "Default")
      (node (ref "R23") (pin "2") (pinfunction "2_2") (pintype "passive"))
      (node (ref "U$4") (pin "1") (pinfunction "-IN_1") (pintype "input"))
      (node (ref "X2") (pin "9") (pinfunction "9_9") (pintype "passive"))
    )
    (net (code "16") (name "F_+5V") (class "Default")
      (node (ref "C1") (pin "2") (pinfunction "2_2") (pintype "passive"))
      (node (ref "C19") (pin "2") (pinfunction "2_2") (pintype "passive"))
      (node (ref "C2") (pin "2") (pinfunction "2_2") (pintype "passive"))
      (node (ref "EK-TM4C1294XL") (pin "2") (pinfunction "+5V_2") (pintype "power_in"))
      (node (ref "EK-TM4C1294XL") (pin "97") (pinfunction "+5V_97") (pintype "power_in"))
      (node (ref "EK-TM4C1294XL") (pin "99") (pinfunction "+5V_99") (pintype "power_in"))
      (node (ref "IC1") (pin "16") (pinfunction "VCC_16") (pintype "power_in"))
      (node (ref "IC2") (pin "16") (pinfunction "VCC_16") (pintype "power_in"))
      (node (ref "JP8") (pin "3") (pinfunction "3_3") (pintype "passive"))
      (node (ref "JP_EK-TM4C1294XL") (pin "1") (pinfunction "+5V_1") (pintype "power_in"))
      (node (ref "JP_EK-TM4C1294XL") (pin "100") (pinfunction "+5V_100") (pintype "power_in"))
      (node (ref "JP_EK-TM4C1294XL") (pin "98") (pinfunction "+5V_98") (pintype "power_in"))
      (node (ref "NT1") (pin "1") (pinfunction "IN0_1") (pintype "passive"))
      (node (ref "NT1") (pin "3") (pinfunction "IN1_3") (pintype "passive"))
      (node (ref "U$6") (pin "3") (pinfunction "ENABLE_3") (pintype "bidirectional"))
      (node (ref "U$6") (pin "4") (pinfunction "IN_4") (pintype "bidirectional"))
    )
    (net (code "17") (name "F_+12V") (class "Default")
      (node (ref "C13") (pin "1") (pinfunction "1_1") (pintype "passive"))
      (node (ref "C15") (pin "1") (pinfunction "1_1") (pintype "passive"))
      (node (ref "C24") (pin "1") (pinfunction "1_1") (pintype "passive"))
      (node (ref "C26") (pin "1") (pinfunction "1_1") (pintype "passive"))
      (node (ref "C28") (pin "1") (pinfunction "1_1") (pintype "passive"))
      (node (ref "C5") (pin "1") (pinfunction "1_1") (pintype "passive"))
      (node (ref "C7") (pin "1") (pinfunction "1_1") (pintype "passive"))
      (node (ref "EK-TM4C1294XL") (pin "100") (pinfunction "+12V_100") (pintype "power_in"))
      (node (ref "IC3") (pin "8") (pinfunction "V+_8") (pintype "power_in"))
      (node (ref "IC4") (pin "8") (pinfunction "V+_8") (pintype "power_in"))
      (node (ref "IC5") (pin "8") (pinfunction "V+_8") (pintype "power_in"))
      (node (ref "JP8") (pin "1") (pinfunction "1_1") (pintype "passive"))
      (node (ref "JP_EK-TM4C1294XL") (pin "99") (pinfunction "+12V_99") (pintype "power_in"))
      (node (ref "R10") (pin "1") (pinfunction "1_1") (pintype "passive"))
      (node (ref "U$1") (pin "8") (pinfunction "V+_8") (pintype "power_in"))
      (node (ref "U$2") (pin "8") (pinfunction "V+_8") (pintype "power_in"))
      (node (ref "U$3") (pin "8") (pinfunction "V+_8") (pintype "power_in"))
      (node (ref "U$4") (pin "8") (pinfunction "V+_8") (pintype "power_in"))
    )
    (net (code "18") (name "F_-12V") (class "Default")
      (node (ref "C14") (pin "2") (pinfunction "2_2") (pintype "passive"))
      (node (ref "C16") (pin "2") (pinfunction "2_2") (pintype "passive"))
      (node (ref "C25") (pin "2") (pinfunction "2_2") (pintype "passive"))
      (node (ref "C27") (pin "2") (pinfunction "2_2") (pintype "passive"))
      (node (ref "C29") (pin "2") (pinfunction "2_2") (pintype "passive"))
      (node (ref "C6") (pin "2") (pinfunction "2_2") (pintype "passive"))
      (node (ref "C8") (pin "2") (pinfunction "2_2") (pintype "passive"))
      (node (ref "EK-TM4C1294XL") (pin "101") (pinfunction "-12V_101") (pintype "power_in"))
      (node (ref "IC3") (pin "4") (pinfunction "V-_4") (pintype "power_in"))
      (node (ref "IC4") (pin "4") (pinfunction "V-_4") (pintype "power_in"))
      (node (ref "IC5") (pin "4") (pinfunction "V-_4") (pintype "power_in"))
      (node (ref "JP_EK-TM4C1294XL") (pin "102") (pinfunction "-12V_102") (pintype "power_in"))
      (node (ref "U$1") (pin "5") (pinfunction "V-_5") (pintype "power_in"))
      (node (ref "U$2") (pin "5") (pinfunction "V-_5") (pintype "power_in"))
      (node (ref "U$3") (pin "5") (pinfunction "V-_5") (pintype "power_in"))
      (node (ref "U$4") (pin "5") (pinfunction "V-_5") (pintype "power_in"))
    )
    (net (code "19") (name "GND") (class "Default")
      (node (ref "C1") (pin "1") (pinfunction "1_1") (pintype "passive"))
      (node (ref "C11") (pin "2") (pinfunction "2_2") (pintype "passive"))
      (node (ref "C15") (pin "2") (pinfunction "2_2") (pintype "passive"))
      (node (ref "C16") (pin "1") (pinfunction "1_1") (pintype "passive"))
      (node (ref "C17") (pin "2") (pinfunction "2_2") (pintype "passive"))
      (node (ref "C19") (pin "1") (pinfunction "1_1") (pintype "passive"))
      (node (ref "C2") (pin "1") (pinfunction "1_1") (pintype "passive"))
      (node (ref "C20") (pin "2") (pinfunction "2_2") (pintype "passive"))
      (node (ref "C21") (pin "1") (pinfunction "1_1") (pintype "passive"))
      (node (ref "C21") (pin "2") (pinfunction "2_2") (pintype "passive"))
      (node (ref "C22") (pin "2") (pinfunction "2_2") (pintype "passive"))
      (node (ref "C23") (pin "-") (pinfunction "-_-") (pintype "passive"))
      (node (ref "C24") (pin "2") (pinfunction "2_2") (pintype "passive"))
      (node (ref "C25") (pin "1") (pinfunction "1_1") (pintype "passive"))
      (node (ref "C26") (pin "2") (pinfunction "2_2") (pintype "passive"))
      (node (ref "C27") (pin "1") (pinfunction "1_1") (pintype "passive"))
      (node (ref "C28") (pin "2") (pinfunction "2_2") (pintype "passive"))
      (node (ref "C29") (pin "1") (pinfunction "1_1") (pintype "passive"))
      (node (ref "C3") (pin "2") (pinfunction "2_2") (pintype "passive"))
      (node (ref "C7") (pin "2") (pinfunction "2_2") (pintype "passive"))
      (node (ref "C8") (pin "1") (pinfunction "1_1") (pintype "passive"))
      (node (ref "C9") (pin "2") (pinfunction "2_2") (pintype "passive"))
      (node (ref "D1") (pin "1") (pinfunction "A1_1") (pintype "passive"))
      (node (ref "D2") (pin "1") (pinfunction "A1_1") (pintype "passive"))
      (node (ref "D3") (pin "1") (pinfunction "A1_1") (pintype "passive"))
      (node (ref "D4") (pin "1") (pinfunction "A1_1") (pintype "passive"))
      (node (ref "DCDC1") (pin "2") (pinfunction "-VIN_2") (pintype "power_in"))
      (node (ref "DCDC1") (pin "6") (pinfunction "-VOUT_6") (pintype "power_in"))
      (node (ref "EK-TM4C1294XL") (pin "102") (pinfunction "GND_102") (pintype "power_in"))
      (node (ref "EK-TM4C1294XL") (pin "3") (pinfunction "GND_3") (pintype "power_in"))
      (node (ref "EK-TM4C1294XL") (pin "35") (pinfunction "GND_35") (pintype "power_in"))
      (node (ref "EK-TM4C1294XL") (pin "36") (pinfunction "GND_36") (pintype "power_in"))
      (node (ref "EK-TM4C1294XL") (pin "4") (pinfunction "GND_4") (pintype "power_in"))
      (node (ref "EK-TM4C1294XL") (pin "61") (pinfunction "GND_61") (pintype "power_in"))
      (node (ref "EK-TM4C1294XL") (pin "62") (pinfunction "GND_62") (pintype "power_in"))
      (node (ref "EK-TM4C1294XL") (pin "96") (pinfunction "GND_96") (pintype "power_in"))
      (node (ref "IC1") (pin "6") (pinfunction "#E_6") (pintype "input"))
      (node (ref "IC1") (pin "7") (pinfunction "VEE_7") (pintype "power_in"))
      (node (ref "IC1") (pin "8") (pinfunction "GND_8") (pintype "power_in"))
      (node (ref "IC2") (pin "6") (pinfunction "#E_6") (pintype "input"))
      (node (ref "IC2") (pin "7") (pinfunction "VEE_7") (pintype "power_in"))
      (node (ref "IC2") (pin "8") (pinfunction "GND_8") (pintype "power_in"))
      (node (ref "JP_EK-TM4C1294XL") (pin "101") (pinfunction "GND_101") (pintype "power_in"))
      (node (ref "JP_EK-TM4C1294XL") (pin "3") (pinfunction "GND_3") (pintype "power_in"))
      (node (ref "JP_EK-TM4C1294XL") (pin "35") (pinfunction "GND_35") (pintype "power_in"))
      (node (ref "JP_EK-TM4C1294XL") (pin "36") (pinfunction "GND_36") (pintype "power_in"))
      (node (ref "JP_EK-TM4C1294XL") (pin "4") (pinfunction "GND_4") (pintype "power_in"))
      (node (ref "JP_EK-TM4C1294XL") (pin "61") (pinfunction "GND_61") (pintype "power_in"))
      (node (ref "JP_EK-TM4C1294XL") (pin "62") (pinfunction "GND_62") (pintype "power_in"))
      (node (ref "JP_EK-TM4C1294XL") (pin "95") (pinfunction "GND_95") (pintype "power_in"))
      (node (ref "R11") (pin "1") (pinfunction "1_1") (pintype "passive"))
      (node (ref "R12") (pin "2") (pinfunction "2_2") (pintype "passive"))
      (node (ref "R13") (pin "2") (pinfunction "2_2") (pintype "passive"))
      (node (ref "R34") (pin "2") (pinfunction "2_2") (pintype "passive"))
      (node (ref "U$6") (pin "1") (pinfunction "GND_F_1") (pintype "bidirectional"))
      (node (ref "U$6") (pin "2") (pinfunction "GND_S_2") (pintype "bidirectional"))
    )
    (net (code "20") (name "MCU_ADC0") (class "Default")
      (node (ref "D1") (pin "3") (pinfunction "C1A2_3") (pintype "passive"))
      (node (ref "JP1") (pin "1") (pinfunction "1_1") (pintype "passive"))
      (node (ref "R30") (pin "2") (pinfunction "2_2") (pintype "passive"))
      (node (ref "R39") (pin "1") (pinfunction "1_1") (pintype "passive"))
    )
    (net (code "21") (name "MCU_ADC1") (class "Default")
      (node (ref "D2") (pin "3") (pinfunction "C1A2_3") (pintype "passive"))
      (node (ref "JP2") (pin "1") (pinfunction "1_1") (pintype "passive"))
      (node (ref "R31") (pin "1") (pinfunction "1_1") (pintype "passive"))
      (node (ref "R35") (pin "1") (pinfunction "1_1") (pintype "passive"))
    )
    (net (code "22") (name "MCU_ADC2") (class "Default")
      (node (ref "D3") (pin "3") (pinfunction "C1A2_3") (pintype "passive"))
      (node (ref "JP4") (pin "1") (pinfunction "1_1") (pintype "passive"))
      (node (ref "R33") (pin "2") (pinfunction "2_2") (pintype "passive"))
      (node (ref "R37") (pin "1") (pinfunction "1_1") (pintype "passive"))
    )
    (net (code "23") (name "MCU_ADC3") (class "Default")
      (node (ref "D4") (pin "3") (pinfunction "C1A2_3") (pintype "passive"))
      (node (ref "JP3") (pin "1") (pinfunction "1_1") (pintype "passive"))
      (node (ref "R32") (pin "1") (pinfunction "1_1") (pintype "passive"))
      (node (ref "R38") (pin "1") (pinfunction "1_1") (pintype "passive"))
    )
    (net (code "24") (name "Net-(C4-Pad1)") (class "Default")
      (node (ref "C4") (pin "1") (pinfunction "1_1") (pintype "passive"))
      (node (ref "R16") (pin "1") (pinfunction "1_1") (pintype "passive"))
      (node (ref "R17") (pin "2") (pinfunction "2_2") (pintype "passive"))
    )
    (net (code "25") (name "Net-(C5-Pad2)") (class "Default")
      (node (ref "C5") (pin "2") (pinfunction "2_2") (pintype "passive"))
      (node (ref "C6") (pin "1") (pinfunction "1_1") (pintype "passive"))
    )
    (net (code "26") (name "Net-(C10-Pad1)") (class "Default")
      (node (ref "C10") (pin "1") (pinfunction "1_1") (pintype "passive"))
      (node (ref "R18") (pin "1") (pinfunction "1_1") (pintype "passive"))
      (node (ref "R19") (pin "2") (pinfunction "2_2") (pintype "passive"))
    )
    (net (code "27") (name "Net-(C12-Pad1)") (class "Default")
      (node (ref "C12") (pin "1") (pinfunction "1_1") (pintype "passive"))
      (node (ref "R26") (pin "1") (pinfunction "1_1") (pintype "passive"))
      (node (ref "R27") (pin "2") (pinfunction "2_2") (pintype "passive"))
    )
    (net (code "28") (name "Net-(C13-Pad2)") (class "Default")
      (node (ref "C13") (pin "2") (pinfunction "2_2") (pintype "passive"))
      (node (ref "C14") (pin "1") (pinfunction "1_1") (pintype "passive"))
    )
    (net (code "29") (name "Net-(C18-Pad1)") (class "Default")
      (node (ref "C18") (pin "1") (pinfunction "1_1") (pintype "passive"))
      (node (ref "R28") (pin "1") (pinfunction "1_1") (pintype "passive"))
      (node (ref "R29") (pin "2") (pinfunction "2_2") (pintype "passive"))
    )
    (net (code "30") (name "Net-(C20-Pad1)") (class "Default")
      (node (ref "C20") (pin "1") (pinfunction "1_1") (pintype "passive"))
      (node (ref "JP8") (pin "2") (pinfunction "2_2") (pintype "passive"))
      (node (ref "L1") (pin "1") (pinfunction "1_1") (pintype "passive"))
    )
    (net (code "31") (name "Net-(DCDC1-+VIN)") (class "Default")
      (node (ref "C22") (pin "1") (pinfunction "1_1") (pintype "passive"))
      (node (ref "DCDC1") (pin "1") (pinfunction "+VIN_1") (pintype "power_in"))
      (node (ref "L1") (pin "2") (pinfunction "2_2") (pintype "passive"))
    )
    (net (code "32") (name "Net-(IC1-A)") (class "Default")
      (node (ref "IC1") (pin "13") (pinfunction "A_13") (pintype "bidirectional"))
      (node (ref "R30") (pin "1") (pinfunction "1_1") (pintype "passive"))
    )
    (net (code "33") (name "Net-(IC1-B)") (class "Default")
      (node (ref "IC1") (pin "3") (pinfunction "B_3") (pintype "bidirectional"))
      (node (ref "R31") (pin "2") (pinfunction "2_2") (pintype "passive"))
    )
    (net (code "34") (name "Net-(IC2-A)") (class "Default")
      (node (ref "IC2") (pin "13") (pinfunction "A_13") (pintype "bidirectional"))
      (node (ref "R33") (pin "1") (pinfunction "1_1") (pintype "passive"))
    )
    (net (code "35") (name "Net-(IC2-B)") (class "Default")
      (node (ref "IC2") (pin "3") (pinfunction "B_3") (pintype "bidirectional"))
      (node (ref "R32") (pin "2") (pinfunction "2_2") (pintype "passive"))
    )
    (net (code "36") (name "Net-(IC4A-+IN)") (class "Default")
      (node (ref "C9") (pin "1") (pinfunction "1_1") (pintype "passive"))
      (node (ref "IC4") (pin "3") (pinfunction "+IN_3") (pintype "input"))
      (node (ref "R19") (pin "1") (pinfunction "1_1") (pintype "passive"))
    )
    (net (code "37") (name "Net-(IC4A--IN)") (class "Default")
      (node (ref "C10") (pin "2") (pinfunction "2_2") (pintype "passive"))
      (node (ref "IC4") (pin "1") (pinfunction "OUT_1") (pintype "output"))
      (node (ref "IC4") (pin "2") (pinfunction "-IN_2") (pintype "input"))
      (node (ref "R39") (pin "2") (pinfunction "2_2") (pintype "passive"))
    )
    (net (code "38") (name "Net-(IC4B-+IN)") (class "Default")
      (node (ref "C3") (pin "1") (pinfunction "1_1") (pintype "passive"))
      (node (ref "IC4") (pin "5") (pinfunction "+IN_5") (pintype "input"))
      (node (ref "R17") (pin "1") (pinfunction "1_1") (pintype "passive"))
    )
    (net (code "39") (name "Net-(IC4B--IN)") (class "Default")
      (node (ref "C4") (pin "2") (pinfunction "2_2") (pintype "passive"))
      (node (ref "IC4") (pin "6") (pinfunction "-IN_6") (pintype "input"))
      (node (ref "IC4") (pin "7") (pinfunction "OUT_7") (pintype "output"))
      (node (ref "R35") (pin "2") (pinfunction "2_2") (pintype "passive"))
    )
    (net (code "40") (name "Net-(IC5A-+IN)") (class "Default")
      (node (ref "C17") (pin "1") (pinfunction "1_1") (pintype "passive"))
      (node (ref "IC5") (pin "3") (pinfunction "+IN_3") (pintype "input"))
      (node (ref "R29") (pin "1") (pinfunction "1_1") (pintype "passive"))
    )
    (net (code "41") (name "Net-(IC5A--IN)") (class "Default")
      (node (ref "C18") (pin "2") (pinfunction "2_2") (pintype "passive"))
      (node (ref "IC5") (pin "1") (pinfunction "OUT_1") (pintype "output"))
      (node (ref "IC5") (pin "2") (pinfunction "-IN_2") (pintype "input"))
      (node (ref "R37") (pin "2") (pinfunction "2_2") (pintype "passive"))
    )
    (net (code "42") (name "Net-(IC5B-+IN)") (class "Default")
      (node (ref "C11") (pin "1") (pinfunction "1_1") (pintype "passive"))
      (node (ref "IC5") (pin "5") (pinfunction "+IN_5") (pintype "input"))
      (node (ref "R27") (pin "1") (pinfunction "1_1") (pintype "passive"))
    )
    (net (code "43") (name "Net-(IC5B--IN)") (class "Default")
      (node (ref "C12") (pin "2") (pinfunction "2_2") (pintype "passive"))
      (node (ref "IC5") (pin "6") (pinfunction "-IN_6") (pintype "input"))
      (node (ref "IC5") (pin "7") (pinfunction "OUT_7") (pintype "output"))
      (node (ref "R38") (pin "2") (pinfunction "2_2") (pintype "passive"))
    )
    (net (code "44") (name "Net-(JP5-Pad1)") (class "Default")
      (node (ref "JP5") (pin "1") (pinfunction "1_1") (pintype "passive"))
      (node (ref "R9") (pin "2") (pinfunction "2_2") (pintype "passive"))
      (node (ref "X2") (pin "15") (pinfunction "15_15") (pintype "passive"))
    )
    (net (code "45") (name "Net-(JP6-Pad1)") (class "Default")
      (node (ref "JP6") (pin "1") (pinfunction "1_1") (pintype "passive"))
      (node (ref "R10") (pin "2") (pinfunction "2_2") (pintype "passive"))
      (node (ref "X2") (pin "5") (pinfunction "5_5") (pintype "passive"))
    )
    (net (code "46") (name "Net-(JP7-Pad1)") (class "Default")
      (node (ref "JP7") (pin "1") (pinfunction "1_1") (pintype "passive"))
      (node (ref "R11") (pin "2") (pinfunction "2_2") (pintype "passive"))
      (node (ref "X2") (pin "10") (pinfunction "10_10") (pintype "passive"))
    )
    (net (code "47") (name "Net-(R7-Pad1)") (class "Default")
      (node (ref "R7") (pin "1") (pinfunction "1_1") (pintype "passive"))
      (node (ref "U$1") (pin "3") (pinfunction "J_3") (pintype "passive"))
    )
    (net (code "48") (name "Net-(R7-Pad2)") (class "Default")
      (node (ref "R7") (pin "2") (pinfunction "2_2") (pintype "passive"))
      (node (ref "U$1") (pin "2") (pinfunction "J_2") (pintype "passive"))
    )
    (net (code "49") (name "Net-(R8-Pad1)") (class "Default")
      (node (ref "R8") (pin "1") (pinfunction "1_1") (pintype "passive"))
      (node (ref "U$2") (pin "3") (pinfunction "J_3") (pintype "passive"))
    )
    (net (code "50") (name "Net-(R8-Pad2)") (class "Default")
      (node (ref "R8") (pin "2") (pinfunction "2_2") (pintype "passive"))
      (node (ref "U$2") (pin "2") (pinfunction "J_2") (pintype "passive"))
    )
    (net (code "51") (name "Net-(R24-Pad1)") (class "Default")
      (node (ref "R24") (pin "1") (pinfunction "1_1") (pintype "passive"))
      (node (ref "U$3") (pin "3") (pinfunction "J_3") (pintype "passive"))
    )
    (net (code "52") (name "Net-(R24-Pad2)") (class "Default")
      (node (ref "R24") (pin "2") (pinfunction "2_2") (pintype "passive"))
      (node (ref "U$3") (pin "2") (pinfunction "J_2") (pintype "passive"))
    )
    (net (code "53") (name "Net-(R25-Pad1)") (class "Default")
      (node (ref "R25") (pin "1") (pinfunction "1_1") (pintype "passive"))
      (node (ref "U$4") (pin "3") (pinfunction "J_3") (pintype "passive"))
    )
    (net (code "54") (name "Net-(R25-Pad2)") (class "Default")
      (node (ref "R25") (pin "2") (pinfunction "2_2") (pintype "passive"))
      (node (ref "U$4") (pin "2") (pinfunction "J_2") (pintype "passive"))
    )
    (net (code "55") (name "Net-(U$1-+IN)") (class "Default")
      (node (ref "R1") (pin "2") (pinfunction "2_2") (pintype "passive"))
      (node (ref "R2") (pin "1") (pinfunction "1_1") (pintype "passive"))
      (node (ref "U$1") (pin "4") (pinfunction "+IN_4") (pintype "input"))
    )
    (net (code "56") (name "Net-(U$1-OUT)") (class "Default")
      (node (ref "R18") (pin "2") (pinfunction "2_2") (pintype "passive"))
      (node (ref "U$1") (pin "7") (pinfunction "OUT_7") (pintype "output"))
    )
    (net (code "57") (name "Net-(U$2-+IN)") (class "Default")
      (node (ref "R4") (pin "2") (pinfunction "2_2") (pintype "passive"))
      (node (ref "R5") (pin "1") (pinfunction "1_1") (pintype "passive"))
      (node (ref "U$2") (pin "4") (pinfunction "+IN_4") (pintype "input"))
    )
    (net (code "58") (name "Net-(U$2-OUT)") (class "Default")
      (node (ref "R16") (pin "2") (pinfunction "2_2") (pintype "passive"))
      (node (ref "U$2") (pin "7") (pinfunction "OUT_7") (pintype "output"))
    )
    (net (code "59") (name "Net-(U$3-+IN)") (class "Default")
      (node (ref "R14") (pin "2") (pinfunction "2_2") (pintype "passive"))
      (node (ref "R20") (pin "1") (pinfunction "1_1") (pintype "passive"))
      (node (ref "U$3") (pin "4") (pinfunction "+IN_4") (pintype "input"))
    )
    (net (code "60") (name "Net-(U$3-OUT)") (class "Default")
      (node (ref "R28") (pin "2") (pinfunction "2_2") (pintype "passive"))
      (node (ref "U$3") (pin "7") (pinfunction "OUT_7") (pintype "output"))
    )
    (net (code "61") (name "Net-(U$4-+IN)") (class "Default")
      (node (ref "R21") (pin "2") (pinfunction "2_2") (pintype "passive"))
      (node (ref "R22") (pin "1") (pinfunction "1_1") (pintype "passive"))
      (node (ref "U$4") (pin "4") (pinfunction "+IN_4") (pintype "input"))
    )
    (net (code "62") (name "Net-(U$4-OUT)") (class "Default")
      (node (ref "R26") (pin "2") (pinfunction "2_2") (pintype "passive"))
      (node (ref "U$4") (pin "7") (pinfunction "OUT_7") (pintype "output"))
    )
    (net (code "63") (name "Net-(U$6-OUT_F)") (class "Default")
      (node (ref "R36") (pin "1") (pinfunction "1_1") (pintype "passive"))
      (node (ref "U$6") (pin "5") (pinfunction "OUT_S_5") (pintype "bidirectional"))
      (node (ref "U$6") (pin "6") (pinfunction "OUT_F_6") (pintype "bidirectional"))
    )
    (net (code "64") (name "PA0") (class "Default")
      (node (ref "EK-TM4C1294XL") (pin "74") (pinfunction "PA0_74") (pintype "bidirectional"))
      (node (ref "JP_EK-TM4C1294XL") (pin "73") (pinfunction "PA0_73") (pintype "bidirectional"))
    )
    (net (code "65") (name "PA1") (class "Default")
      (node (ref "EK-TM4C1294XL") (pin "76") (pinfunction "PA1_76") (pintype "bidirectional"))
      (node (ref "JP_EK-TM4C1294XL") (pin "75") (pinfunction "PA1_75") (pintype "bidirectional"))
    )
    (net (code "66") (name "PA2") (class "Default")
      (node (ref "EK-TM4C1294XL") (pin "6") (pinfunction "PA2_6") (pintype "bidirectional"))
      (node (ref "JP_EK-TM4C1294XL") (pin "5") (pinfunction "PA2_5") (pintype "bidirectional"))
    )
    (net (code "67") (name "PA3") (class "Default")
      (node (ref "EK-TM4C1294XL") (pin "8") (pinfunction "PA3_8") (pintype "bidirectional"))
      (node (ref "JP_EK-TM4C1294XL") (pin "7") (pinfunction "PA3_7") (pintype "bidirectional"))
    )
    (net (code "68") (name "PA4") (class "Default")
      (node (ref "EK-TM4C1294XL") (pin "10") (pinfunction "PA4_10") (pintype "bidirectional"))
      (node (ref "JP_EK-TM4C1294XL") (pin "9") (pinfunction "PA4_9") (pintype "bidirectional"))
    )
    (net (code "69") (name "PA5") (class "Default")
      (node (ref "EK-TM4C1294XL") (pin "12") (pinfunction "PA5_12") (pintype "bidirectional"))
      (node (ref "JP_EK-TM4C1294XL") (pin "11") (pinfunction "PA5_11") (pintype "bidirectional"))
    )
    (net (code "70") (name "PA6") (class "Default")
      (node (ref "EK-TM4C1294XL") (pin "25") (pinfunction "PA6_25") (pintype "bidirectional"))
      (node (ref "JP_EK-TM4C1294XL") (pin "26") (pinfunction "PA6_26") (pintype "bidirectional"))
    )
    (net (code "71") (name "PA7") (class "Default")
      (node (ref "EK-TM4C1294XL") (pin "27") (pinfunction "PA7_27") (pintype "bidirectional"))
      (node (ref "JP_EK-TM4C1294XL") (pin "28") (pinfunction "PA7_28") (pintype "bidirectional"))
    )
    (net (code "72") (name "PB0") (class "Default")
      (node (ref "EK-TM4C1294XL") (pin "58") (pinfunction "PB0_58") (pintype "bidirectional"))
      (node (ref "JP_EK-TM4C1294XL") (pin "57") (pinfunction "PB0_57") (pintype "bidirectional"))
    )
    (net (code "73") (name "PB1") (class "Default")
      (node (ref "EK-TM4C1294XL") (pin "60") (pinfunction "PB1_60") (pintype "bidirectional"))
      (node (ref "JP_EK-TM4C1294XL") (pin "59") (pinfunction "PB1_59") (pintype "bidirectional"))
    )
    (net (code "74") (name "PB2") (class "Default")
      (node (ref "EK-TM4C1294XL") (pin "67") (pinfunction "PB2_67") (pintype "bidirectional"))
      (node (ref "JP_EK-TM4C1294XL") (pin "68") (pinfunction "PB2_68") (pintype "bidirectional"))
    )
    (net (code "75") (name "PB3") (class "Default")
      (node (ref "EK-TM4C1294XL") (pin "69") (pinfunction "PB3_69") (pintype "bidirectional"))
      (node (ref "JP_EK-TM4C1294XL") (pin "70") (pinfunction "PB3_70") (pintype "bidirectional"))
    )
    (net (code "76") (name "PB4") (class "Default")
      (node (ref "EK-TM4C1294XL") (pin "5") (pinfunction "PB4_5") (pintype "bidirectional"))
      (node (ref "IC2") (pin "15") (pinfunction "A2_15") (pintype "bidirectional"))
      (node (ref "JP_EK-TM4C1294XL") (pin "6") (pinfunction "PB4_6") (pintype "bidirectional"))
    )
    (net (code "77") (name "PB5") (class "Default")
      (node (ref "EK-TM4C1294XL") (pin "7") (pinfunction "PB5_7") (pintype "bidirectional"))
      (node (ref "IC2") (pin "2") (pinfunction "B2_2") (pintype "bidirectional"))
      (node (ref "JP_EK-TM4C1294XL") (pin "8") (pinfunction "PB5_8") (pintype "bidirectional"))
    )
    (net (code "78") (name "PC4") (class "Default")
      (node (ref "EK-TM4C1294XL") (pin "23") (pinfunction "PC4_23") (pintype "bidirectional"))
      (node (ref "JP_EK-TM4C1294XL") (pin "24") (pinfunction "PC4_24") (pintype "bidirectional"))
    )
    (net (code "79") (name "PC5") (class "Default")
      (node (ref "EK-TM4C1294XL") (pin "21") (pinfunction "PC5_21") (pintype "bidirectional"))
      (node (ref "JP_EK-TM4C1294XL") (pin "22") (pinfunction "PC5_22") (pintype "bidirectional"))
    )
    (net (code "80") (name "PC6") (class "Default")
      (node (ref "EK-TM4C1294XL") (pin "19") (pinfunction "PC6_19") (pintype "bidirectional"))
      (node (ref "JP_EK-TM4C1294XL") (pin "20") (pinfunction "PC6_20") (pintype "bidirectional"))
    )
    (net (code "81") (name "PC7") (class "Default")
      (node (ref "EK-TM4C1294XL") (pin "17") (pinfunction "PC7_17") (pintype "bidirectional"))
      (node (ref "JP_EK-TM4C1294XL") (pin "18") (pinfunction "PC7_18") (pintype "bidirectional"))
    )
    (net (code "82") (name "PD0") (class "Default")
      (node (ref "EK-TM4C1294XL") (pin "50") (pinfunction "PD0_50") (pintype "bidirectional"))
      (node (ref "IC2") (pin "4") (pinfunction "B3_4") (pintype "bidirectional"))
      (node (ref "JP_EK-TM4C1294XL") (pin "49") (pinfunction "PD0_49") (pintype "bidirectional"))
    )
    (net (code "83") (name "PD1") (class "Default")
      (node (ref "EK-TM4C1294XL") (pin "48") (pinfunction "PD1_48") (pintype "bidirectional"))
      (node (ref "IC2") (pin "11") (pinfunction "A3_11") (pintype "bidirectional"))
      (node (ref "JP_EK-TM4C1294XL") (pin "47") (pinfunction "PD1_47") (pintype "bidirectional"))
    )
    (net (code "84") (name "PD2") (class "Default")
      (node (ref "EK-TM4C1294XL") (pin "52") (pinfunction "PD2_52") (pintype "bidirectional"))
      (node (ref "IC1") (pin "4") (pinfunction "B3_4") (pintype "bidirectional"))
      (node (ref "JP_EK-TM4C1294XL") (pin "51") (pinfunction "PD2_51") (pintype "bidirectional"))
    )
    (net (code "85") (name "PD3") (class "Default")
      (node (ref "EK-TM4C1294XL") (pin "46") (pinfunction "PD3_46") (pintype "bidirectional"))
      (node (ref "IC1") (pin "11") (pinfunction "A3_11") (pintype "bidirectional"))
      (node (ref "JP_EK-TM4C1294XL") (pin "45") (pinfunction "PD3_45") (pintype "bidirectional"))
    )
    (net (code "86") (name "PD4") (class "Default")
      (node (ref "EK-TM4C1294XL") (pin "40") (pinfunction "PD4_40") (pintype "bidirectional"))
      (node (ref "IC2") (pin "5") (pinfunction "B1_5") (pintype "bidirectional"))
      (node (ref "JP_EK-TM4C1294XL") (pin "39") (pinfunction "PD4_39") (pintype "bidirectional"))
    )
    (net (code "87") (name "PD5") (class "Default")
      (node (ref "EK-TM4C1294XL") (pin "38") (pinfunction "PD5_38") (pintype "bidirectional"))
      (node (ref "IC2") (pin "14") (pinfunction "A1_14") (pintype "bidirectional"))
      (node (ref "JP_EK-TM4C1294XL") (pin "37") (pinfunction "PD5_37") (pintype "bidirectional"))
    )
    (net (code "88") (name "PD6") (class "Default")
      (node (ref "EK-TM4C1294XL") (pin "44") (pinfunction "PD6_44") (pintype "bidirectional"))
      (node (ref "IC1") (pin "5") (pinfunction "B1_5") (pintype "bidirectional"))
      (node (ref "JP_EK-TM4C1294XL") (pin "43") (pinfunction "PD6_43") (pintype "bidirectional"))
    )
    (net (code "89") (name "PD7") (class "Default")
      (node (ref "EK-TM4C1294XL") (pin "42") (pinfunction "PD7_42") (pintype "bidirectional"))
      (node (ref "IC1") (pin "14") (pinfunction "A1_14") (pintype "bidirectional"))
      (node (ref "JP_EK-TM4C1294XL") (pin "41") (pinfunction "PD7_41") (pintype "bidirectional"))
    )
    (net (code "90") (name "PE0") (class "Default")
      (node (ref "EK-TM4C1294XL") (pin "14") (pinfunction "PE0_14") (pintype "bidirectional"))
      (node (ref "IC2") (pin "1") (pinfunction "B0_1") (pintype "bidirectional"))
      (node (ref "JP_EK-TM4C1294XL") (pin "13") (pinfunction "PE0_13") (pintype "bidirectional"))
    )
    (net (code "91") (name "PE1") (class "Default")
      (node (ref "EK-TM4C1294XL") (pin "16") (pinfunction "PE1_16") (pintype "bidirectional"))
      (node (ref "IC2") (pin "12") (pinfunction "A0_12") (pintype "bidirectional"))
      (node (ref "JP_EK-TM4C1294XL") (pin "15") (pinfunction "PE1_15") (pintype "bidirectional"))
    )
    (net (code "92") (name "PE2") (class "Default")
      (node (ref "EK-TM4C1294XL") (pin "18") (pinfunction "PE2_18") (pintype "bidirectional"))
      (node (ref "IC1") (pin "1") (pinfunction "B0_1") (pintype "bidirectional"))
      (node (ref "JP_EK-TM4C1294XL") (pin "17") (pinfunction "PE2_17") (pintype "bidirectional"))
    )
    (net (code "93") (name "PE3") (class "Default")
      (node (ref "EK-TM4C1294XL") (pin "20") (pinfunction "PE3_20") (pintype "bidirectional"))
      (node (ref "IC1") (pin "12") (pinfunction "A0_12") (pintype "bidirectional"))
      (node (ref "JP_EK-TM4C1294XL") (pin "19") (pinfunction "PE3_19") (pintype "bidirectional"))
    )
    (net (code "94") (name "PE4") (class "Default")
      (node (ref "EK-TM4C1294XL") (pin "22") (pinfunction "PE4_22") (pintype "bidirectional"))
      (node (ref "IC1") (pin "2") (pinfunction "B2_2") (pintype "bidirectional"))
      (node (ref "JP_EK-TM4C1294XL") (pin "21") (pinfunction "PE4_21") (pintype "bidirectional"))
    )
    (net (code "95") (name "PE5") (class "Default")
      (node (ref "EK-TM4C1294XL") (pin "24") (pinfunction "PE5_24") (pintype "bidirectional"))
      (node (ref "IC1") (pin "15") (pinfunction "A2_15") (pintype "bidirectional"))
      (node (ref "JP_EK-TM4C1294XL") (pin "23") (pinfunction "PE5_23") (pintype "bidirectional"))
    )
    (net (code "96") (name "PF0") (class "Default")
      (node (ref "EK-TM4C1294XL") (pin "66") (pinfunction "PF0_66") (pintype "bidirectional"))
      (node (ref "JP_EK-TM4C1294XL") (pin "65") (pinfunction "PF0_65") (pintype "bidirectional"))
    )
    (net (code "97") (name "PF1") (class "Default")
      (node (ref "EK-TM4C1294XL") (pin "68") (pinfunction "PF1_68") (pintype "bidirectional"))
      (node (ref "JP_EK-TM4C1294XL") (pin "67") (pinfunction "PF1_67") (pintype "bidirectional"))
    )
    (net (code "98") (name "PF2") (class "Default")
      (node (ref "EK-TM4C1294XL") (pin "70") (pinfunction "PF2_70") (pintype "bidirectional"))
      (node (ref "JP_EK-TM4C1294XL") (pin "69") (pinfunction "PF2_69") (pintype "bidirectional"))
    )
    (net (code "99") (name "PF3") (class "Default")
      (node (ref "EK-TM4C1294XL") (pin "72") (pinfunction "PF3_72") (pintype "bidirectional"))
      (node (ref "JP_EK-TM4C1294XL") (pin "71") (pinfunction "PF3_71") (pintype "bidirectional"))
    )
    (net (code "100") (name "PF4") (class "Default")
      (node (ref "EK-TM4C1294XL") (pin "64") (pinfunction "PF4_64") (pintype "bidirectional"))
      (node (ref "JP_EK-TM4C1294XL") (pin "63") (pinfunction "PF4_63") (pintype "bidirectional"))
    )
    (net (code "101") (name "PG0") (class "Default")
      (node (ref "EK-TM4C1294XL") (pin "31") (pinfunction "PG0_31") (pintype "bidirectional"))
      (node (ref "JP_EK-TM4C1294XL") (pin "32") (pinfunction "PG0_32") (pintype "bidirectional"))
    )
    (net (code "102") (name "PG1") (class "Default")
      (node (ref "EK-TM4C1294XL") (pin "29") (pinfunction "PG1_29") (pintype "bidirectional"))
      (node (ref "JP_EK-TM4C1294XL") (pin "30") (pinfunction "PG1_30") (pintype "bidirectional"))
    )
    (net (code "103") (name "PH0") (class "Default")
      (node (ref "EK-TM4C1294XL") (pin "9") (pinfunction "PH0_9") (pintype "bidirectional"))
      (node (ref "JP_EK-TM4C1294XL") (pin "10") (pinfunction "PH0_10") (pintype "bidirectional"))
    )
    (net (code "104") (name "PH1") (class "Default")
      (node (ref "EK-TM4C1294XL") (pin "11") (pinfunction "PH1_11") (pintype "bidirectional"))
      (node (ref "JP_EK-TM4C1294XL") (pin "12") (pinfunction "PH1_12") (pintype "bidirectional"))
    )
    (net (code "105") (name "PH2") (class "Default")
      (node (ref "EK-TM4C1294XL") (pin "13") (pinfunction "PH2_13") (pintype "bidirectional"))
      (node (ref "JP_EK-TM4C1294XL") (pin "14") (pinfunction "PH2_14") (pintype "bidirectional"))
    )
    (net (code "106") (name "PH3") (class "Default")
      (node (ref "EK-TM4C1294XL") (pin "15") (pinfunction "PH3_15") (pintype "bidirectional"))
      (node (ref "JP_EK-TM4C1294XL") (pin "16") (pinfunction "PH3_16") (pintype "bidirectional"))
    )
    (net (code "107") (name "PJ0") (class "Default")
      (node (ref "EK-TM4C1294XL") (pin "82") (pinfunction "PJ0_82") (pintype "bidirectional"))
      (node (ref "JP_EK-TM4C1294XL") (pin "81") (pinfunction "PJ0_81") (pintype "bidirectional"))
    )
    (net (code "108") (name "PJ1") (class "Default")
      (node (ref "EK-TM4C1294XL") (pin "84") (pinfunction "PJ1_84") (pintype "bidirectional"))
      (node (ref "JP_EK-TM4C1294XL") (pin "83") (pinfunction "PJ1_83") (pintype "bidirectional"))
    )
    (net (code "109") (name "PK0") (class "Default")
      (node (ref "EK-TM4C1294XL") (pin "26") (pinfunction "PK0_26") (pintype "bidirectional"))
      (node (ref "JP_EK-TM4C1294XL") (pin "25") (pinfunction "PK0_25") (pintype "bidirectional"))
    )
    (net (code "110") (name "PK1") (class "Default")
      (node (ref "EK-TM4C1294XL") (pin "28") (pinfunction "PK1_28") (pintype "bidirectional"))
      (node (ref "JP_EK-TM4C1294XL") (pin "27") (pinfunction "PK1_27") (pintype "bidirectional"))
    )
    (net (code "111") (name "PK2") (class "Default")
      (node (ref "EK-TM4C1294XL") (pin "30") (pinfunction "PK2_30") (pintype "bidirectional"))
      (node (ref "JP_EK-TM4C1294XL") (pin "29") (pinfunction "PK2_29") (pintype "bidirectional"))
    )
    (net (code "112") (name "PK3") (class "Default")
      (node (ref "EK-TM4C1294XL") (pin "32") (pinfunction "PK3_32") (pintype "bidirectional"))
      (node (ref "JP_EK-TM4C1294XL") (pin "31") (pinfunction "PK3_31") (pintype "bidirectional"))
    )
    (net (code "113") (name "PK4") (class "Default")
      (node (ref "EK-TM4C1294XL") (pin "77") (pinfunction "PK4_77") (pintype "bidirectional"))
      (node (ref "JP_EK-TM4C1294XL") (pin "78") (pinfunction "PK4_78") (pintype "bidirectional"))
    )
    (net (code "114") (name "PK5") (class "Default")
      (node (ref "EK-TM4C1294XL") (pin "75") (pinfunction "PK5_75") (pintype "bidirectional"))
      (node (ref "JP_EK-TM4C1294XL") (pin "76") (pinfunction "PK5_76") (pintype "bidirectional"))
    )
    (net (code "115") (name "PK6") (class "Default")
      (node (ref "EK-TM4C1294XL") (pin "63") (pinfunction "PK6_63") (pintype "bidirectional"))
      (node (ref "JP_EK-TM4C1294XL") (pin "64") (pinfunction "PK6_64") (pintype "bidirectional"))
    )
    (net (code "116") (name "PK7") (class "Default")
      (node (ref "EK-TM4C1294XL") (pin "59") (pinfunction "PK7_59") (pintype "bidirectional"))
      (node (ref "JP_EK-TM4C1294XL") (pin "60") (pinfunction "PK7_60") (pintype "bidirectional"))
    )
    (net (code "117") (name "PL0") (class "Default")
      (node (ref "EK-TM4C1294XL") (pin "43") (pinfunction "PL0_43") (pintype "bidirectional"))
      (node (ref "JP_EK-TM4C1294XL") (pin "44") (pinfunction "PL0_44") (pintype "bidirectional"))
    )
    (net (code "118") (name "PL1") (class "Default")
      (node (ref "EK-TM4C1294XL") (pin "45") (pinfunction "PL1_45") (pintype "bidirectional"))
      (node (ref "JP_EK-TM4C1294XL") (pin "46") (pinfunction "PL1_46") (pintype "bidirectional"))
    )
    (net (code "119") (name "PL2") (class "Default")
      (node (ref "EK-TM4C1294XL") (pin "47") (pinfunction "PL2_47") (pintype "bidirectional"))
      (node (ref "JP_EK-TM4C1294XL") (pin "48") (pinfunction "PL2_48") (pintype "bidirectional"))
    )
    (net (code "120") (name "PL3") (class "Default")
      (node (ref "EK-TM4C1294XL") (pin "49") (pinfunction "PL3_49") (pintype "bidirectional"))
      (node (ref "JP_EK-TM4C1294XL") (pin "50") (pinfunction "PL3_50") (pintype "bidirectional"))
    )
    (net (code "121") (name "PL4") (class "Default")
      (node (ref "EK-TM4C1294XL") (pin "65") (pinfunction "PL4_65") (pintype "bidirectional"))
      (node (ref "JP_EK-TM4C1294XL") (pin "66") (pinfunction "PL4_66") (pintype "bidirectional"))
    )
    (net (code "122") (name "PL5") (class "Default")
      (node (ref "EK-TM4C1294XL") (pin "79") (pinfunction "PL5_79") (pintype "bidirectional"))
      (node (ref "JP_EK-TM4C1294XL") (pin "80") (pinfunction "PL5_80") (pintype "bidirectional"))
    )
    (net (code "123") (name "PM0") (class "Default")
      (node (ref "EK-TM4C1294XL") (pin "41") (pinfunction "PM0_41") (pintype "bidirectional"))
      (node (ref "JP_EK-TM4C1294XL") (pin "42") (pinfunction "PM0_42") (pintype "bidirectional"))
    )
    (net (code "124") (name "PM1") (class "Default")
      (node (ref "EK-TM4C1294XL") (pin "39") (pinfunction "PM1_39") (pintype "bidirectional"))
      (node (ref "JP_EK-TM4C1294XL") (pin "40") (pinfunction "PM1_40") (pintype "bidirectional"))
    )
    (net (code "125") (name "PM2") (class "Default")
      (node (ref "EK-TM4C1294XL") (pin "37") (pinfunction "PM2_37") (pintype "bidirectional"))
      (node (ref "JP_EK-TM4C1294XL") (pin "38") (pinfunction "PM2_38") (pintype "bidirectional"))
    )
    (net (code "126") (name "PM3") (class "Default")
      (node (ref "EK-TM4C1294XL") (pin "33") (pinfunction "PM3_33") (pintype "bidirectional"))
      (node (ref "JP_EK-TM4C1294XL") (pin "34") (pinfunction "PM3_34") (pintype "bidirectional"))
    )
    (net (code "127") (name "PM4") (class "Default")
      (node (ref "EK-TM4C1294XL") (pin "92") (pinfunction "PM4_92") (pintype "bidirectional"))
      (node (ref "JP_EK-TM4C1294XL") (pin "91") (pinfunction "PM4_91") (pintype "bidirectional"))
    )
    (net (code "128") (name "PM5") (class "Default")
      (node (ref "EK-TM4C1294XL") (pin "90") (pinfunction "PM5_90") (pintype "bidirectional"))
      (node (ref "JP_EK-TM4C1294XL") (pin "89") (pinfunction "PM5_89") (pintype "bidirectional"))
    )
    (net (code "129") (name "PM6") (class "Default")
      (node (ref "EK-TM4C1294XL") (pin "88") (pinfunction "PM6_88") (pintype "bidirectional"))
      (node (ref "JP_EK-TM4C1294XL") (pin "87") (pinfunction "PM6_87") (pintype "bidirectional"))
    )
    (net (code "130") (name "PM7") (class "Default")
      (node (ref "EK-TM4C1294XL") (pin "86") (pinfunction "PM7_86") (pintype "bidirectional"))
      (node (ref "JP_EK-TM4C1294XL") (pin "85") (pinfunction "PM7_85") (pintype "bidirectional"))
    )
    (net (code "131") (name "PN0") (class "Default")
      (node (ref "EK-TM4C1294XL") (pin "85") (pinfunction "PN0_85") (pintype "bidirectional"))
      (node (ref "JP_EK-TM4C1294XL") (pin "86") (pinfunction "PN0_86") (pintype "bidirectional"))
    )
    (net (code "132") (name "PN1") (class "Default")
      (node (ref "EK-TM4C1294XL") (pin "87") (pinfunction "PN1_87") (pintype "bidirectional"))
      (node (ref "JP_EK-TM4C1294XL") (pin "88") (pinfunction "PN1_88") (pintype "bidirectional"))
    )
    (net (code "133") (name "PN2") (class "Default")
      (node (ref "EK-TM4C1294XL") (pin "89") (pinfunction "PN2_89") (pintype "bidirectional"))
      (node (ref "JP_EK-TM4C1294XL") (pin "90") (pinfunction "PN2_90") (pintype "bidirectional"))
    )
    (net (code "134") (name "PN3") (class "Default")
      (node (ref "EK-TM4C1294XL") (pin "91") (pinfunction "PN3_91") (pintype "bidirectional"))
      (node (ref "JP_EK-TM4C1294XL") (pin "92") (pinfunction "PN3_92") (pintype "bidirectional"))
    )
    (net (code "135") (name "PN4") (class "Default")
      (node (ref "EK-TM4C1294XL") (pin "81") (pinfunction "PN4_81") (pintype "bidirectional"))
      (node (ref "JP_EK-TM4C1294XL") (pin "82") (pinfunction "PN4_82") (pintype "bidirectional"))
    )
    (net (code "136") (name "PN5") (class "Default")
      (node (ref "EK-TM4C1294XL") (pin "83") (pinfunction "PN5_83") (pintype "bidirectional"))
      (node (ref "JP_EK-TM4C1294XL") (pin "84") (pinfunction "PN5_84") (pintype "bidirectional"))
    )
    (net (code "137") (name "PP0") (class "Default")
      (node (ref "EK-TM4C1294XL") (pin "54") (pinfunction "PP0_54") (pintype "bidirectional"))
      (node (ref "JP_EK-TM4C1294XL") (pin "53") (pinfunction "PP0_53") (pintype "bidirectional"))
    )
    (net (code "138") (name "PP1") (class "Default")
      (node (ref "EK-TM4C1294XL") (pin "56") (pinfunction "PP1_56") (pintype "bidirectional"))
      (node (ref "JP_EK-TM4C1294XL") (pin "55") (pinfunction "PP1_55") (pintype "bidirectional"))
    )
    (net (code "139") (name "PP2") (class "Default")
      (node (ref "EK-TM4C1294XL") (pin "71") (pinfunction "PP2_71") (pintype "bidirectional"))
      (node (ref "JP_EK-TM4C1294XL") (pin "72") (pinfunction "PP2_72") (pintype "bidirectional"))
    )
    (net (code "140") (name "PP3") (class "Default")
      (node (ref "EK-TM4C1294XL") (pin "73") (pinfunction "PP3_73") (pintype "bidirectional"))
      (node (ref "JP_EK-TM4C1294XL") (pin "74") (pinfunction "PP3_74") (pintype "bidirectional"))
    )
    (net (code "141") (name "PP4") (class "Default")
      (node (ref "EK-TM4C1294XL") (pin "78") (pinfunction "PP4_78") (pintype "bidirectional"))
      (node (ref "JP_EK-TM4C1294XL") (pin "77") (pinfunction "PP4_77") (pintype "bidirectional"))
    )
    (net (code "142") (name "PP5") (class "Default")
      (node (ref "EK-TM4C1294XL") (pin "80") (pinfunction "PP5_80") (pintype "bidirectional"))
      (node (ref "JP_EK-TM4C1294XL") (pin "79") (pinfunction "PP5_79") (pintype "bidirectional"))
    )
    (net (code "143") (name "PQ0") (class "Default")
      (node (ref "EK-TM4C1294XL") (pin "51") (pinfunction "PQ0_51") (pintype "bidirectional"))
      (node (ref "JP_EK-TM4C1294XL") (pin "52") (pinfunction "PQ0_52") (pintype "bidirectional"))
    )
    (net (code "144") (name "PQ1") (class "Default")
      (node (ref "EK-TM4C1294XL") (pin "53") (pinfunction "PQ1_53") (pintype "bidirectional"))
      (node (ref "JP_EK-TM4C1294XL") (pin "54") (pinfunction "PQ1_54") (pintype "bidirectional"))
    )
    (net (code "145") (name "PQ2") (class "Default")
      (node (ref "EK-TM4C1294XL") (pin "55") (pinfunction "PQ2_55") (pintype "bidirectional"))
      (node (ref "JP_EK-TM4C1294XL") (pin "56") (pinfunction "PQ2_56") (pintype "bidirectional"))
    )
    (net (code "146") (name "PQ3") (class "Default")
      (node (ref "EK-TM4C1294XL") (pin "57") (pinfunction "PQ3_57") (pintype "bidirectional"))
      (node (ref "JP_EK-TM4C1294XL") (pin "58") (pinfunction "PQ3_58") (pintype "bidirectional"))
    )
    (net (code "147") (name "PQ4") (class "Default")
      (node (ref "EK-TM4C1294XL") (pin "93") (pinfunction "PQ4_93") (pintype "bidirectional"))
      (node (ref "JP_EK-TM4C1294XL") (pin "94") (pinfunction "PQ4_94") (pintype "bidirectional"))
    )
    (net (code "148") (name "REF") (class "Default")
      (node (ref "IC3") (pin "1") (pinfunction "OUT_1") (pintype "output"))
      (node (ref "IC3") (pin "2") (pinfunction "-IN_2") (pintype "input"))
      (node (ref "U$1") (pin "6") (pinfunction "REF_6") (pintype "passive"))
      (node (ref "U$2") (pin "6") (pinfunction "REF_6") (pintype "passive"))
      (node (ref "U$3") (pin "6") (pinfunction "REF_6") (pintype "passive"))
      (node (ref "U$4") (pin "6") (pinfunction "REF_6") (pintype "passive"))
    )
    (net (code "149") (name "RESET") (class "Default")
      (node (ref "EK-TM4C1294XL") (pin "94") (pinfunction "RESET_94") (pintype "bidirectional"))
      (node (ref "JP_EK-TM4C1294XL") (pin "93") (pinfunction "RESET_93") (pintype "bidirectional"))
    )
    (net (code "150") (name "SW0") (class "Default")
      (node (ref "IC1") (pin "10") (pinfunction "S0_10") (pintype "input"))
      (node (ref "IC2") (pin "10") (pinfunction "S0_10") (pintype "input"))
      (node (ref "NT1") (pin "2") (pinfunction "OUT0_2") (pintype "passive"))
      (node (ref "R13") (pin "1") (pinfunction "1_1") (pintype "passive"))
    )
    (net (code "151") (name "SW1") (class "Default")
      (node (ref "IC1") (pin "9") (pinfunction "S1_9") (pintype "input"))
      (node (ref "IC2") (pin "9") (pinfunction "S1_9") (pintype "input"))
      (node (ref "NT1") (pin "4") (pinfunction "OUT1_4") (pintype "passive"))
      (node (ref "R12") (pin "1") (pinfunction "1_1") (pintype "passive"))
    )
    (net (code "152") (name "VREF") (class "Default")
      (node (ref "EK-TM4C1294XL") (pin "34") (pinfunction "VREF_34") (pintype "input"))
      (node (ref "JP_EK-TM4C1294XL") (pin "33") (pinfunction "VREF_33") (pintype "input"))
    )
    (net (code "153") (name "WAKE") (class "Default")
      (node (ref "EK-TM4C1294XL") (pin "95") (pinfunction "WAKE_95") (pintype "bidirectional"))
      (node (ref "JP_EK-TM4C1294XL") (pin "96") (pinfunction "WAKE_96") (pintype "bidirectional"))
    )
    (net (code "154") (name "unconnected-(DCDC1-ON{slash}OFF-Pad4)") (class "Default")
      (node (ref "DCDC1") (pin "4") (pinfunction "ON/OFF_4") (pintype "input"))
    )
  )
)
